# vivepos-v1-1.net
KiCad netlist of a schematic drawn in EAGLE
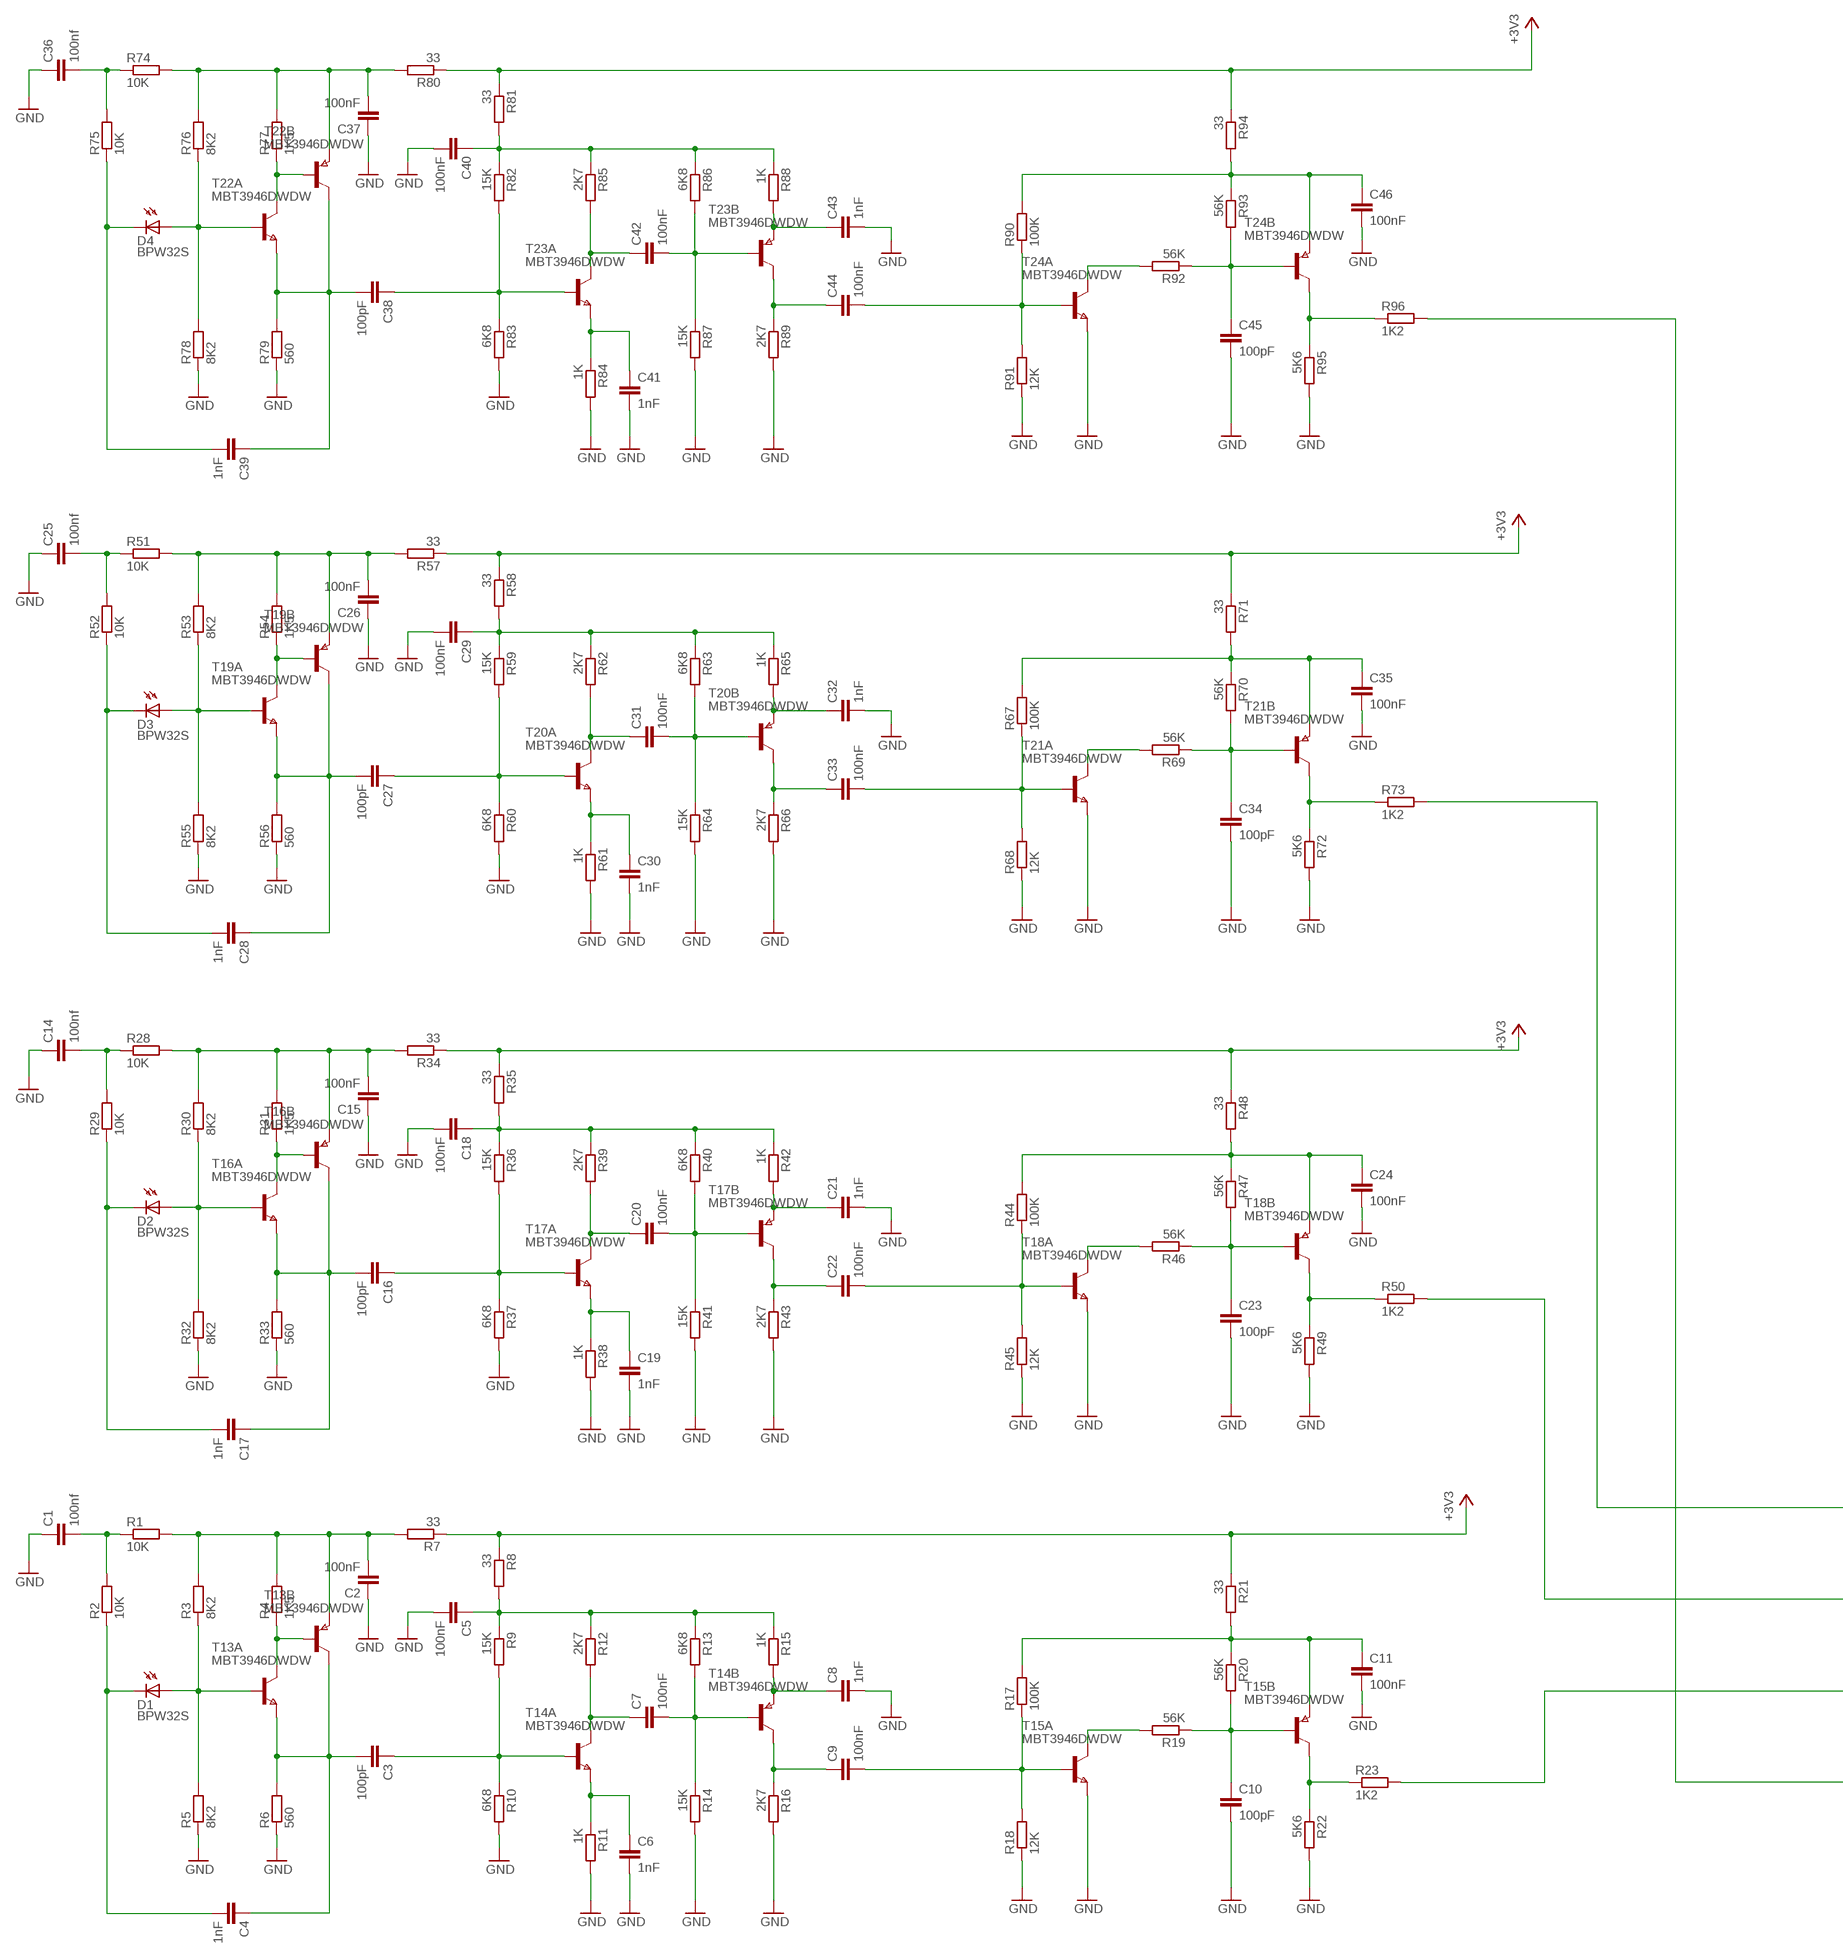
[diagram p0: schematic, sheet 1, part 1 of 2]
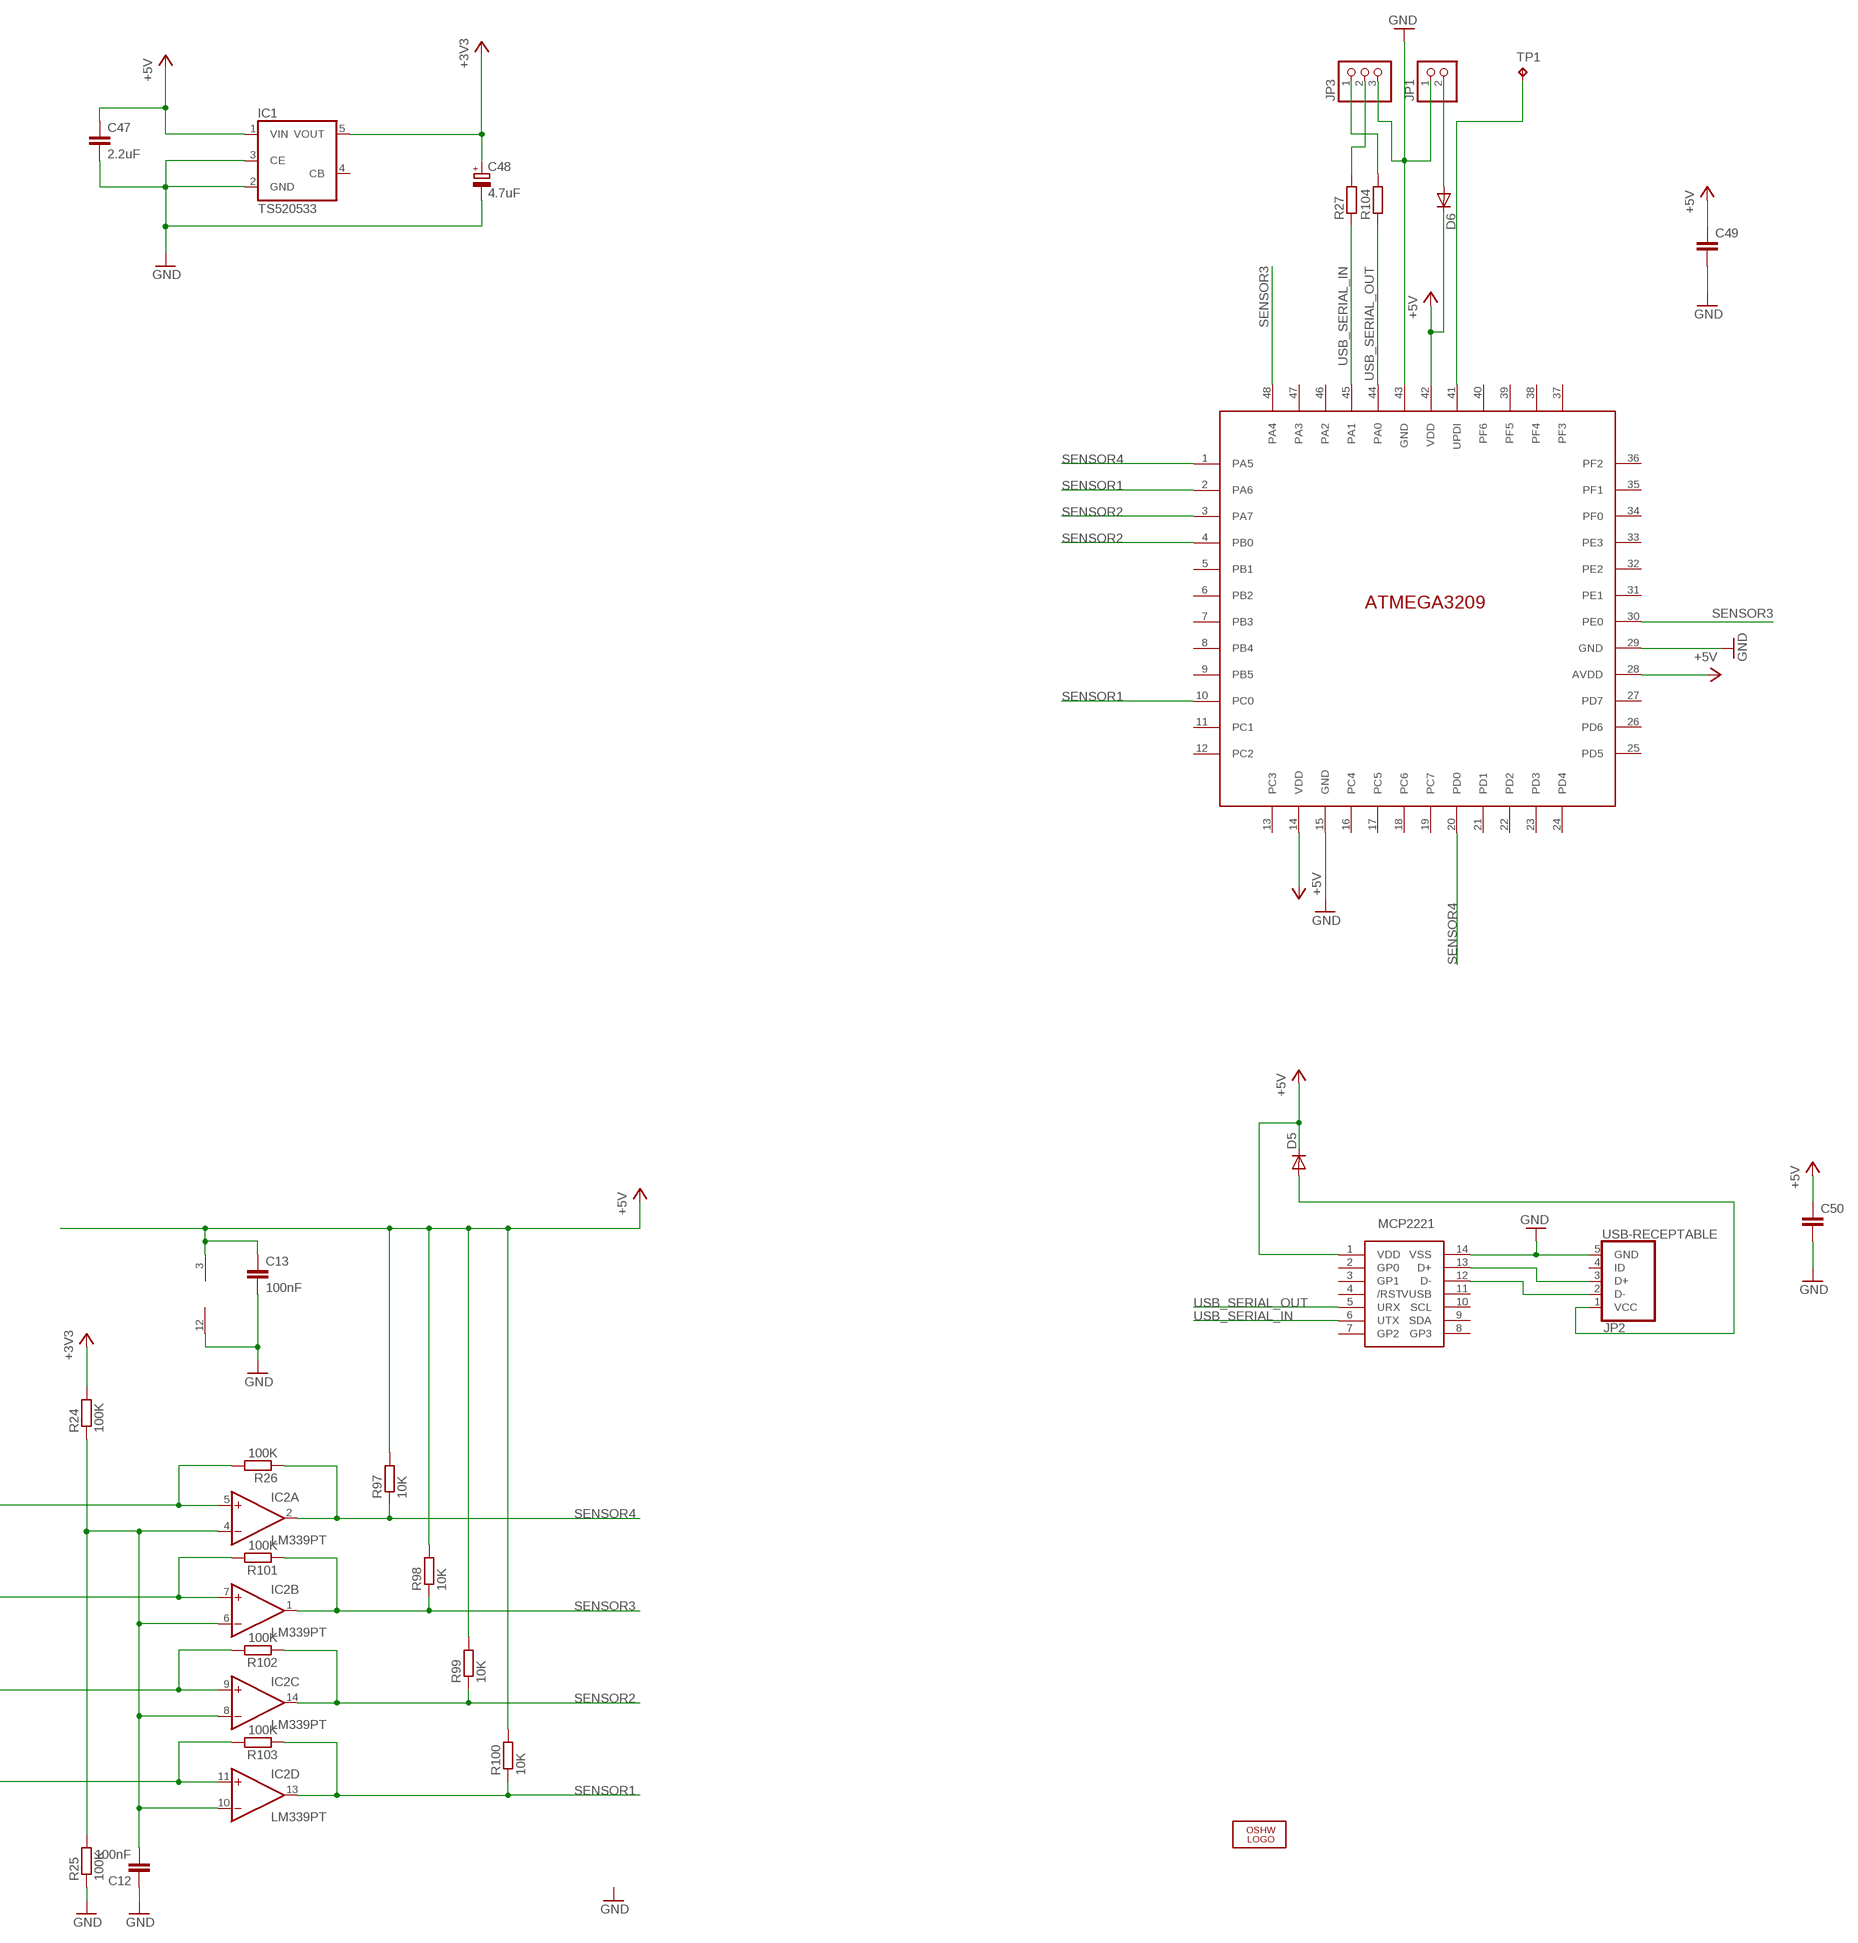
[diagram p1: schematic, sheet 1, part 2 of 2]

(export (version "E")
  (design (tool "Eeschema 10.0.6"))
  (components
    (comp (ref "C1")
      (value "100nf")
      (footprint "eagle-import:C0402")
      (libsource (lib "eagle-import") (part "C-EUC0402"))
    )
    (comp (ref "C2")
      (value "100nF")
      (footprint "eagle-import:C0402")
      (libsource (lib "eagle-import") (part "C-EUC0402"))
    )
    (comp (ref "C3")
      (value "100pF")
      (footprint "eagle-import:C0402")
      (libsource (lib "eagle-import") (part "C-EUC0402"))
    )
    (comp (ref "C4")
      (value "1nF")
      (footprint "eagle-import:C0402")
      (libsource (lib "eagle-import") (part "C-EUC0402"))
    )
    (comp (ref "C5")
      (value "100nF")
      (footprint "eagle-import:C0402")
      (libsource (lib "eagle-import") (part "C-EUC0402"))
    )
    (comp (ref "C6")
      (value "1nF")
      (footprint "eagle-import:C0402")
      (libsource (lib "eagle-import") (part "C-EUC0402"))
    )
    (comp (ref "C7")
      (value "100nF")
      (footprint "eagle-import:C0402")
      (libsource (lib "eagle-import") (part "C-EUC0402"))
    )
    (comp (ref "C8")
      (value "1nF")
      (footprint "eagle-import:C0402")
      (libsource (lib "eagle-import") (part "C-EUC0402"))
    )
    (comp (ref "C9")
      (value "100nF")
      (footprint "eagle-import:C0402")
      (libsource (lib "eagle-import") (part "C-EUC0402"))
    )
    (comp (ref "C10")
      (value "100pF")
      (footprint "eagle-import:C0402")
      (libsource (lib "eagle-import") (part "C-EUC0402"))
    )
    (comp (ref "C11")
      (value "100nF")
      (footprint "eagle-import:C0402")
      (libsource (lib "eagle-import") (part "C-EUC0402"))
    )
    (comp (ref "C12")
      (value "100nF")
      (footprint "eagle-import:C0402")
      (libsource (lib "eagle-import") (part "C-EUC0402"))
    )
    (comp (ref "C13")
      (value "100nF")
      (footprint "eagle-import:C0402")
      (libsource (lib "eagle-import") (part "C-EUC0402"))
    )
    (comp (ref "C14")
      (value "100nf")
      (footprint "eagle-import:C0402")
      (libsource (lib "eagle-import") (part "C-EUC0402"))
    )
    (comp (ref "C15")
      (value "100nF")
      (footprint "eagle-import:C0402")
      (libsource (lib "eagle-import") (part "C-EUC0402"))
    )
    (comp (ref "C16")
      (value "100pF")
      (footprint "eagle-import:C0402")
      (libsource (lib "eagle-import") (part "C-EUC0402"))
    )
    (comp (ref "C17")
      (value "1nF")
      (footprint "eagle-import:C0402")
      (libsource (lib "eagle-import") (part "C-EUC0402"))
    )
    (comp (ref "C18")
      (value "100nF")
      (footprint "eagle-import:C0402")
      (libsource (lib "eagle-import") (part "C-EUC0402"))
    )
    (comp (ref "C19")
      (value "1nF")
      (footprint "eagle-import:C0402")
      (libsource (lib "eagle-import") (part "C-EUC0402"))
    )
    (comp (ref "C20")
      (value "100nF")
      (footprint "eagle-import:C0402")
      (libsource (lib "eagle-import") (part "C-EUC0402"))
    )
    (comp (ref "C21")
      (value "1nF")
      (footprint "eagle-import:C0402")
      (libsource (lib "eagle-import") (part "C-EUC0402"))
    )
    (comp (ref "C22")
      (value "100nF")
      (footprint "eagle-import:C0402")
      (libsource (lib "eagle-import") (part "C-EUC0402"))
    )
    (comp (ref "C23")
      (value "100pF")
      (footprint "eagle-import:C0402")
      (libsource (lib "eagle-import") (part "C-EUC0402"))
    )
    (comp (ref "C24")
      (value "100nF")
      (footprint "eagle-import:C0402")
      (libsource (lib "eagle-import") (part "C-EUC0402"))
    )
    (comp (ref "C25")
      (value "100nf")
      (footprint "eagle-import:C0402")
      (libsource (lib "eagle-import") (part "C-EUC0402"))
    )
    (comp (ref "C26")
      (value "100nF")
      (footprint "eagle-import:C0402")
      (libsource (lib "eagle-import") (part "C-EUC0402"))
    )
    (comp (ref "C27")
      (value "100pF")
      (footprint "eagle-import:C0402")
      (libsource (lib "eagle-import") (part "C-EUC0402"))
    )
    (comp (ref "C28")
      (value "1nF")
      (footprint "eagle-import:C0402")
      (libsource (lib "eagle-import") (part "C-EUC0402"))
    )
    (comp (ref "C29")
      (value "100nF")
      (footprint "eagle-import:C0402")
      (libsource (lib "eagle-import") (part "C-EUC0402"))
    )
    (comp (ref "C30")
      (value "1nF")
      (footprint "eagle-import:C0402")
      (libsource (lib "eagle-import") (part "C-EUC0402"))
    )
    (comp (ref "C31")
      (value "100nF")
      (footprint "eagle-import:C0402")
      (libsource (lib "eagle-import") (part "C-EUC0402"))
    )
    (comp (ref "C32")
      (value "1nF")
      (footprint "eagle-import:C0402")
      (libsource (lib "eagle-import") (part "C-EUC0402"))
    )
    (comp (ref "C33")
      (value "100nF")
      (footprint "eagle-import:C0402")
      (libsource (lib "eagle-import") (part "C-EUC0402"))
    )
    (comp (ref "C34")
      (value "100pF")
      (footprint "eagle-import:C0402")
      (libsource (lib "eagle-import") (part "C-EUC0402"))
    )
    (comp (ref "C35")
      (value "100nF")
      (footprint "eagle-import:C0402")
      (libsource (lib "eagle-import") (part "C-EUC0402"))
    )
    (comp (ref "C36")
      (value "100nf")
      (footprint "eagle-import:C0402")
      (libsource (lib "eagle-import") (part "C-EUC0402"))
    )
    (comp (ref "C37")
      (value "100nF")
      (footprint "eagle-import:C0402")
      (libsource (lib "eagle-import") (part "C-EUC0402"))
    )
    (comp (ref "C38")
      (value "100pF")
      (footprint "eagle-import:C0402")
      (libsource (lib "eagle-import") (part "C-EUC0402"))
    )
    (comp (ref "C39")
      (value "1nF")
      (footprint "eagle-import:C0402")
      (libsource (lib "eagle-import") (part "C-EUC0402"))
    )
    (comp (ref "C40")
      (value "100nF")
      (footprint "eagle-import:C0402")
      (libsource (lib "eagle-import") (part "C-EUC0402"))
    )
    (comp (ref "C41")
      (value "1nF")
      (footprint "eagle-import:C0402")
      (libsource (lib "eagle-import") (part "C-EUC0402"))
    )
    (comp (ref "C42")
      (value "100nF")
      (footprint "eagle-import:C0402")
      (libsource (lib "eagle-import") (part "C-EUC0402"))
    )
    (comp (ref "C43")
      (value "1nF")
      (footprint "eagle-import:C0402")
      (libsource (lib "eagle-import") (part "C-EUC0402"))
    )
    (comp (ref "C44")
      (value "100nF")
      (footprint "eagle-import:C0402")
      (libsource (lib "eagle-import") (part "C-EUC0402"))
    )
    (comp (ref "C45")
      (value "100pF")
      (footprint "eagle-import:C0402")
      (libsource (lib "eagle-import") (part "C-EUC0402"))
    )
    (comp (ref "C46")
      (value "100nF")
      (footprint "eagle-import:C0402")
      (libsource (lib "eagle-import") (part "C-EUC0402"))
    )
    (comp (ref "C47")
      (value "2.2uF")
      (footprint "eagle-import:C0805")
      (libsource (lib "eagle-import") (part "C-EUC0805"))
    )
    (comp (ref "C48")
      (value "4.7uF")
      (footprint "eagle-import:B_3528-21R")
      (libsource (lib "eagle-import") (part "CPOL-EUB/3528-21R"))
    )
    (comp (ref "C49")
      (value "C-EUC0402")
      (footprint "eagle-import:C0402")
      (libsource (lib "eagle-import") (part "C-EUC0402"))
    )
    (comp (ref "C50")
      (value "C-EUC0603")
      (footprint "eagle-import:C0603")
      (libsource (lib "eagle-import") (part "C-EUC0603"))
    )
    (comp (ref "D1")
      (value "BPW32S")
      (footprint "eagle-import:BPW34S")
      (libsource (lib "eagle-import") (part "BPW32S"))
    )
    (comp (ref "D2")
      (value "BPW32S")
      (footprint "eagle-import:BPW34S")
      (libsource (lib "eagle-import") (part "BPW32S"))
    )
    (comp (ref "D3")
      (value "BPW32S")
      (footprint "eagle-import:BPW34S")
      (libsource (lib "eagle-import") (part "BPW32S"))
    )
    (comp (ref "D4")
      (value "BPW32S")
      (footprint "eagle-import:BPW34S")
      (libsource (lib "eagle-import") (part "BPW32S"))
    )
    (comp (ref "D5")
      (value "DIODE-SOD323-W")
      (footprint "eagle-import:SOD323-W")
      (libsource (lib "eagle-import") (part "DIODE-SOD323-W"))
    )
    (comp (ref "D6")
      (value "DIODE-SOD323-W")
      (footprint "eagle-import:SOD323-W")
      (libsource (lib "eagle-import") (part "DIODE-SOD323-W"))
    )
    (comp (ref "IC1")
      (value "TS520533")
      (footprint "eagle-import:SOT25")
      (libsource (lib "eagle-import") (part "TS520533"))
    )
    (comp (ref "IC2")
      (value "LM339PT")
      (footprint "eagle-import:TSSOP14")
      (libsource (lib "eagle-import") (part "LM339PT"))
    )
    (comp (ref "JP1")
      (value "PINHD-1X2")
      (footprint "eagle-import:1X02")
      (libsource (lib "eagle-import") (part "PINHD-1X2"))
    )
    (comp (ref "JP2")
      (value "USB-RECEPTABLE")
      (footprint "eagle-import:FCI-10103594-0001LF")
      (libsource (lib "eagle-import") (part "USB-RECEPTABLE"))
    )
    (comp (ref "JP3")
      (value "PINHD-1X3")
      (footprint "eagle-import:1X03")
      (libsource (lib "eagle-import") (part "PINHD-1X3"))
    )
    (comp (ref "LOGO1")
      (value "OSHW_LOGO_FILLX0200-NT")
      (footprint "eagle-import:OSHW_FILLX200_NOTEXT")
      (libsource (lib "eagle-import") (part "OSHW_LOGO_FILLX0200-NT"))
    )
    (comp (ref "R1")
      (value "10K")
      (footprint "eagle-import:R0402")
      (libsource (lib "eagle-import") (part "R-EU_R0402"))
    )
    (comp (ref "R2")
      (value "10K")
      (footprint "eagle-import:R0402")
      (libsource (lib "eagle-import") (part "R-EU_R0402"))
    )
    (comp (ref "R3")
      (value "8K2")
      (footprint "eagle-import:R0402")
      (libsource (lib "eagle-import") (part "R-EU_R0402"))
    )
    (comp (ref "R4")
      (value "1K5")
      (footprint "eagle-import:R0402")
      (libsource (lib "eagle-import") (part "R-EU_R0402"))
    )
    (comp (ref "R5")
      (value "8K2")
      (footprint "eagle-import:R0402")
      (libsource (lib "eagle-import") (part "R-EU_R0402"))
    )
    (comp (ref "R6")
      (value "560")
      (footprint "eagle-import:R0402")
      (libsource (lib "eagle-import") (part "R-EU_R0402"))
    )
    (comp (ref "R7")
      (value "33")
      (footprint "eagle-import:R0402")
      (libsource (lib "eagle-import") (part "R-EU_R0402"))
    )
    (comp (ref "R8")
      (value "33")
      (footprint "eagle-import:R0402")
      (libsource (lib "eagle-import") (part "R-EU_R0402"))
    )
    (comp (ref "R9")
      (value "15K")
      (footprint "eagle-import:R0402")
      (libsource (lib "eagle-import") (part "R-EU_R0402"))
    )
    (comp (ref "R10")
      (value "6K8")
      (footprint "eagle-import:R0402")
      (libsource (lib "eagle-import") (part "R-EU_R0402"))
    )
    (comp (ref "R11")
      (value "1K")
      (footprint "eagle-import:R0402")
      (libsource (lib "eagle-import") (part "R-EU_R0402"))
    )
    (comp (ref "R12")
      (value "2K7")
      (footprint "eagle-import:R0402")
      (libsource (lib "eagle-import") (part "R-EU_R0402"))
    )
    (comp (ref "R13")
      (value "6K8")
      (footprint "eagle-import:R0402")
      (libsource (lib "eagle-import") (part "R-EU_R0402"))
    )
    (comp (ref "R14")
      (value "15K")
      (footprint "eagle-import:R0402")
      (libsource (lib "eagle-import") (part "R-EU_R0402"))
    )
    (comp (ref "R15")
      (value "1K")
      (footprint "eagle-import:R0402")
      (libsource (lib "eagle-import") (part "R-EU_R0402"))
    )
    (comp (ref "R16")
      (value "2K7")
      (footprint "eagle-import:R0402")
      (libsource (lib "eagle-import") (part "R-EU_R0402"))
    )
    (comp (ref "R17")
      (value "100K")
      (footprint "eagle-import:R0402")
      (libsource (lib "eagle-import") (part "R-EU_R0402"))
    )
    (comp (ref "R18")
      (value "12K")
      (footprint "eagle-import:R0402")
      (libsource (lib "eagle-import") (part "R-EU_R0402"))
    )
    (comp (ref "R19")
      (value "56K")
      (footprint "eagle-import:R0402")
      (libsource (lib "eagle-import") (part "R-EU_R0402"))
    )
    (comp (ref "R20")
      (value "56K")
      (footprint "eagle-import:R0402")
      (libsource (lib "eagle-import") (part "R-EU_R0402"))
    )
    (comp (ref "R21")
      (value "33")
      (footprint "eagle-import:R0402")
      (libsource (lib "eagle-import") (part "R-EU_R0402"))
    )
    (comp (ref "R22")
      (value "5K6")
      (footprint "eagle-import:R0402")
      (libsource (lib "eagle-import") (part "R-EU_R0402"))
    )
    (comp (ref "R23")
      (value "1K2")
      (footprint "eagle-import:R0402")
      (libsource (lib "eagle-import") (part "R-EU_R0402"))
    )
    (comp (ref "R24")
      (value "100K")
      (footprint "eagle-import:R0402")
      (libsource (lib "eagle-import") (part "R-EU_R0402"))
    )
    (comp (ref "R25")
      (value "100K")
      (footprint "eagle-import:R0402")
      (libsource (lib "eagle-import") (part "R-EU_R0402"))
    )
    (comp (ref "R26")
      (value "100K")
      (footprint "eagle-import:R0402")
      (libsource (lib "eagle-import") (part "R-EU_R0402"))
    )
    (comp (ref "R27")
      (value "R-EU_R0402")
      (footprint "eagle-import:R0402")
      (libsource (lib "eagle-import") (part "R-EU_R0402"))
    )
    (comp (ref "R28")
      (value "10K")
      (footprint "eagle-import:R0402")
      (libsource (lib "eagle-import") (part "R-EU_R0402"))
    )
    (comp (ref "R29")
      (value "10K")
      (footprint "eagle-import:R0402")
      (libsource (lib "eagle-import") (part "R-EU_R0402"))
    )
    (comp (ref "R30")
      (value "8K2")
      (footprint "eagle-import:R0402")
      (libsource (lib "eagle-import") (part "R-EU_R0402"))
    )
    (comp (ref "R31")
      (value "1K5")
      (footprint "eagle-import:R0402")
      (libsource (lib "eagle-import") (part "R-EU_R0402"))
    )
    (comp (ref "R32")
      (value "8K2")
      (footprint "eagle-import:R0402")
      (libsource (lib "eagle-import") (part "R-EU_R0402"))
    )
    (comp (ref "R33")
      (value "560")
      (footprint "eagle-import:R0402")
      (libsource (lib "eagle-import") (part "R-EU_R0402"))
    )
    (comp (ref "R34")
      (value "33")
      (footprint "eagle-import:R0402")
      (libsource (lib "eagle-import") (part "R-EU_R0402"))
    )
    (comp (ref "R35")
      (value "33")
      (footprint "eagle-import:R0402")
      (libsource (lib "eagle-import") (part "R-EU_R0402"))
    )
    (comp (ref "R36")
      (value "15K")
      (footprint "eagle-import:R0402")
      (libsource (lib "eagle-import") (part "R-EU_R0402"))
    )
    (comp (ref "R37")
      (value "6K8")
      (footprint "eagle-import:R0402")
      (libsource (lib "eagle-import") (part "R-EU_R0402"))
    )
    (comp (ref "R38")
      (value "1K")
      (footprint "eagle-import:R0402")
      (libsource (lib "eagle-import") (part "R-EU_R0402"))
    )
    (comp (ref "R39")
      (value "2K7")
      (footprint "eagle-import:R0402")
      (libsource (lib "eagle-import") (part "R-EU_R0402"))
    )
    (comp (ref "R40")
      (value "6K8")
      (footprint "eagle-import:R0402")
      (libsource (lib "eagle-import") (part "R-EU_R0402"))
    )
    (comp (ref "R41")
      (value "15K")
      (footprint "eagle-import:R0402")
      (libsource (lib "eagle-import") (part "R-EU_R0402"))
    )
    (comp (ref "R42")
      (value "1K")
      (footprint "eagle-import:R0402")
      (libsource (lib "eagle-import") (part "R-EU_R0402"))
    )
    (comp (ref "R43")
      (value "2K7")
      (footprint "eagle-import:R0402")
      (libsource (lib "eagle-import") (part "R-EU_R0402"))
    )
    (comp (ref "R44")
      (value "100K")
      (footprint "eagle-import:R0402")
      (libsource (lib "eagle-import") (part "R-EU_R0402"))
    )
    (comp (ref "R45")
      (value "12K")
      (footprint "eagle-import:R0402")
      (libsource (lib "eagle-import") (part "R-EU_R0402"))
    )
    (comp (ref "R46")
      (value "56K")
      (footprint "eagle-import:R0402")
      (libsource (lib "eagle-import") (part "R-EU_R0402"))
    )
    (comp (ref "R47")
      (value "56K")
      (footprint "eagle-import:R0402")
      (libsource (lib "eagle-import") (part "R-EU_R0402"))
    )
    (comp (ref "R48")
      (value "33")
      (footprint "eagle-import:R0402")
      (libsource (lib "eagle-import") (part "R-EU_R0402"))
    )
    (comp (ref "R49")
      (value "5K6")
      (footprint "eagle-import:R0402")
      (libsource (lib "eagle-import") (part "R-EU_R0402"))
    )
    (comp (ref "R50")
      (value "1K2")
      (footprint "eagle-import:R0402")
      (libsource (lib "eagle-import") (part "R-EU_R0402"))
    )
    (comp (ref "R51")
      (value "10K")
      (footprint "eagle-import:R0402")
      (libsource (lib "eagle-import") (part "R-EU_R0402"))
    )
    (comp (ref "R52")
      (value "10K")
      (footprint "eagle-import:R0402")
      (libsource (lib "eagle-import") (part "R-EU_R0402"))
    )
    (comp (ref "R53")
      (value "8K2")
      (footprint "eagle-import:R0402")
      (libsource (lib "eagle-import") (part "R-EU_R0402"))
    )
    (comp (ref "R54")
      (value "1K5")
      (footprint "eagle-import:R0402")
      (libsource (lib "eagle-import") (part "R-EU_R0402"))
    )
    (comp (ref "R55")
      (value "8K2")
      (footprint "eagle-import:R0402")
      (libsource (lib "eagle-import") (part "R-EU_R0402"))
    )
    (comp (ref "R56")
      (value "560")
      (footprint "eagle-import:R0402")
      (libsource (lib "eagle-import") (part "R-EU_R0402"))
    )
    (comp (ref "R57")
      (value "33")
      (footprint "eagle-import:R0402")
      (libsource (lib "eagle-import") (part "R-EU_R0402"))
    )
    (comp (ref "R58")
      (value "33")
      (footprint "eagle-import:R0402")
      (libsource (lib "eagle-import") (part "R-EU_R0402"))
    )
    (comp (ref "R59")
      (value "15K")
      (footprint "eagle-import:R0402")
      (libsource (lib "eagle-import") (part "R-EU_R0402"))
    )
    (comp (ref "R60")
      (value "6K8")
      (footprint "eagle-import:R0402")
      (libsource (lib "eagle-import") (part "R-EU_R0402"))
    )
    (comp (ref "R61")
      (value "1K")
      (footprint "eagle-import:R0402")
      (libsource (lib "eagle-import") (part "R-EU_R0402"))
    )
    (comp (ref "R62")
      (value "2K7")
      (footprint "eagle-import:R0402")
      (libsource (lib "eagle-import") (part "R-EU_R0402"))
    )
    (comp (ref "R63")
      (value "6K8")
      (footprint "eagle-import:R0402")
      (libsource (lib "eagle-import") (part "R-EU_R0402"))
    )
    (comp (ref "R64")
      (value "15K")
      (footprint "eagle-import:R0402")
      (libsource (lib "eagle-import") (part "R-EU_R0402"))
    )
    (comp (ref "R65")
      (value "1K")
      (footprint "eagle-import:R0402")
      (libsource (lib "eagle-import") (part "R-EU_R0402"))
    )
    (comp (ref "R66")
      (value "2K7")
      (footprint "eagle-import:R0402")
      (libsource (lib "eagle-import") (part "R-EU_R0402"))
    )
    (comp (ref "R67")
      (value "100K")
      (footprint "eagle-import:R0402")
      (libsource (lib "eagle-import") (part "R-EU_R0402"))
    )
    (comp (ref "R68")
      (value "12K")
      (footprint "eagle-import:R0402")
      (libsource (lib "eagle-import") (part "R-EU_R0402"))
    )
    (comp (ref "R69")
      (value "56K")
      (footprint "eagle-import:R0402")
      (libsource (lib "eagle-import") (part "R-EU_R0402"))
    )
    (comp (ref "R70")
      (value "56K")
      (footprint "eagle-import:R0402")
      (libsource (lib "eagle-import") (part "R-EU_R0402"))
    )
    (comp (ref "R71")
      (value "33")
      (footprint "eagle-import:R0402")
      (libsource (lib "eagle-import") (part "R-EU_R0402"))
    )
    (comp (ref "R72")
      (value "5K6")
      (footprint "eagle-import:R0402")
      (libsource (lib "eagle-import") (part "R-EU_R0402"))
    )
    (comp (ref "R73")
      (value "1K2")
      (footprint "eagle-import:R0402")
      (libsource (lib "eagle-import") (part "R-EU_R0402"))
    )
    (comp (ref "R74")
      (value "10K")
      (footprint "eagle-import:R0402")
      (libsource (lib "eagle-import") (part "R-EU_R0402"))
    )
    (comp (ref "R75")
      (value "10K")
      (footprint "eagle-import:R0402")
      (libsource (lib "eagle-import") (part "R-EU_R0402"))
    )
    (comp (ref "R76")
      (value "8K2")
      (footprint "eagle-import:R0402")
      (libsource (lib "eagle-import") (part "R-EU_R0402"))
    )
    (comp (ref "R77")
      (value "1K5")
      (footprint "eagle-import:R0402")
      (libsource (lib "eagle-import") (part "R-EU_R0402"))
    )
    (comp (ref "R78")
      (value "8K2")
      (footprint "eagle-import:R0402")
      (libsource (lib "eagle-import") (part "R-EU_R0402"))
    )
    (comp (ref "R79")
      (value "560")
      (footprint "eagle-import:R0402")
      (libsource (lib "eagle-import") (part "R-EU_R0402"))
    )
    (comp (ref "R80")
      (value "33")
      (footprint "eagle-import:R0402")
      (libsource (lib "eagle-import") (part "R-EU_R0402"))
    )
    (comp (ref "R81")
      (value "33")
      (footprint "eagle-import:R0402")
      (libsource (lib "eagle-import") (part "R-EU_R0402"))
    )
    (comp (ref "R82")
      (value "15K")
      (footprint "eagle-import:R0402")
      (libsource (lib "eagle-import") (part "R-EU_R0402"))
    )
    (comp (ref "R83")
      (value "6K8")
      (footprint "eagle-import:R0402")
      (libsource (lib "eagle-import") (part "R-EU_R0402"))
    )
    (comp (ref "R84")
      (value "1K")
      (footprint "eagle-import:R0402")
      (libsource (lib "eagle-import") (part "R-EU_R0402"))
    )
    (comp (ref "R85")
      (value "2K7")
      (footprint "eagle-import:R0402")
      (libsource (lib "eagle-import") (part "R-EU_R0402"))
    )
    (comp (ref "R86")
      (value "6K8")
      (footprint "eagle-import:R0402")
      (libsource (lib "eagle-import") (part "R-EU_R0402"))
    )
    (comp (ref "R87")
      (value "15K")
      (footprint "eagle-import:R0402")
      (libsource (lib "eagle-import") (part "R-EU_R0402"))
    )
    (comp (ref "R88")
      (value "1K")
      (footprint "eagle-import:R0402")
      (libsource (lib "eagle-import") (part "R-EU_R0402"))
    )
    (comp (ref "R89")
      (value "2K7")
      (footprint "eagle-import:R0402")
      (libsource (lib "eagle-import") (part "R-EU_R0402"))
    )
    (comp (ref "R90")
      (value "100K")
      (footprint "eagle-import:R0402")
      (libsource (lib "eagle-import") (part "R-EU_R0402"))
    )
    (comp (ref "R91")
      (value "12K")
      (footprint "eagle-import:R0402")
      (libsource (lib "eagle-import") (part "R-EU_R0402"))
    )
    (comp (ref "R92")
      (value "56K")
      (footprint "eagle-import:R0402")
      (libsource (lib "eagle-import") (part "R-EU_R0402"))
    )
    (comp (ref "R93")
      (value "56K")
      (footprint "eagle-import:R0402")
      (libsource (lib "eagle-import") (part "R-EU_R0402"))
    )
    (comp (ref "R94")
      (value "33")
      (footprint "eagle-import:R0402")
      (libsource (lib "eagle-import") (part "R-EU_R0402"))
    )
    (comp (ref "R95")
      (value "5K6")
      (footprint "eagle-import:R0402")
      (libsource (lib "eagle-import") (part "R-EU_R0402"))
    )
    (comp (ref "R96")
      (value "1K2")
      (footprint "eagle-import:R0402")
      (libsource (lib "eagle-import") (part "R-EU_R0402"))
    )
    (comp (ref "R97")
      (value "10K")
      (footprint "eagle-import:R0402")
      (libsource (lib "eagle-import") (part "R-EU_R0402"))
    )
    (comp (ref "R98")
      (value "10K")
      (footprint "eagle-import:R0402")
      (libsource (lib "eagle-import") (part "R-EU_R0402"))
    )
    (comp (ref "R99")
      (value "10K")
      (footprint "eagle-import:R0402")
      (libsource (lib "eagle-import") (part "R-EU_R0402"))
    )
    (comp (ref "R100")
      (value "10K")
      (footprint "eagle-import:R0402")
      (libsource (lib "eagle-import") (part "R-EU_R0402"))
    )
    (comp (ref "R101")
      (value "100K")
      (footprint "eagle-import:R0402")
      (libsource (lib "eagle-import") (part "R-EU_R0402"))
    )
    (comp (ref "R102")
      (value "100K")
      (footprint "eagle-import:R0402")
      (libsource (lib "eagle-import") (part "R-EU_R0402"))
    )
    (comp (ref "R103")
      (value "100K")
      (footprint "eagle-import:R0402")
      (libsource (lib "eagle-import") (part "R-EU_R0402"))
    )
    (comp (ref "R104")
      (value "R-EU_R0402")
      (footprint "eagle-import:R0402")
      (libsource (lib "eagle-import") (part "R-EU_R0402"))
    )
    (comp (ref "T13")
      (value "MBT3946DWDW")
      (footprint "eagle-import:SOT363_PHILIPS")
      (libsource (lib "eagle-import") (part "MBT3946DWDW"))
    )
    (comp (ref "T14")
      (value "MBT3946DWDW")
      (footprint "eagle-import:SOT363_PHILIPS")
      (libsource (lib "eagle-import") (part "MBT3946DWDW"))
    )
    (comp (ref "T15")
      (value "MBT3946DWDW")
      (footprint "eagle-import:SOT363_PHILIPS")
      (libsource (lib "eagle-import") (part "MBT3946DWDW"))
    )
    (comp (ref "T16")
      (value "MBT3946DWDW")
      (footprint "eagle-import:SOT363_PHILIPS")
      (libsource (lib "eagle-import") (part "MBT3946DWDW"))
    )
    (comp (ref "T17")
      (value "MBT3946DWDW")
      (footprint "eagle-import:SOT363_PHILIPS")
      (libsource (lib "eagle-import") (part "MBT3946DWDW"))
    )
    (comp (ref "T18")
      (value "MBT3946DWDW")
      (footprint "eagle-import:SOT363_PHILIPS")
      (libsource (lib "eagle-import") (part "MBT3946DWDW"))
    )
    (comp (ref "T19")
      (value "MBT3946DWDW")
      (footprint "eagle-import:SOT363_PHILIPS")
      (libsource (lib "eagle-import") (part "MBT3946DWDW"))
    )
    (comp (ref "T20")
      (value "MBT3946DWDW")
      (footprint "eagle-import:SOT363_PHILIPS")
      (libsource (lib "eagle-import") (part "MBT3946DWDW"))
    )
    (comp (ref "T21")
      (value "MBT3946DWDW")
      (footprint "eagle-import:SOT363_PHILIPS")
      (libsource (lib "eagle-import") (part "MBT3946DWDW"))
    )
    (comp (ref "T22")
      (value "MBT3946DWDW")
      (footprint "eagle-import:SOT363_PHILIPS")
      (libsource (lib "eagle-import") (part "MBT3946DWDW"))
    )
    (comp (ref "T23")
      (value "MBT3946DWDW")
      (footprint "eagle-import:SOT363_PHILIPS")
      (libsource (lib "eagle-import") (part "MBT3946DWDW"))
    )
    (comp (ref "T24")
      (value "MBT3946DWDW")
      (footprint "eagle-import:SOT363_PHILIPS")
      (libsource (lib "eagle-import") (part "MBT3946DWDW"))
    )
    (comp (ref "TP1")
      (value "TPTP15R")
      (footprint "eagle-import:TP15R")
      (libsource (lib "eagle-import") (part "TPTP15R"))
    )
    (comp (ref "U$1")
      (value "MCP2221")
      (footprint "eagle-import:SOIC14")
      (libsource (lib "eagle-import") (part "MCP2221"))
    )
    (comp (ref "U$2")
      (value "ATMEGA3209")
      (footprint "eagle-import:TQFP48")
      (libsource (lib "eagle-import") (part "ATMEGA3209"))
    )
  )
  (nets
    (net (code "1") (name "+3V3") (class "Default")
      (node (ref "C48") (pin "+") (pinfunction "+_+") (pintype "passive"))
      (node (ref "IC1") (pin "5") (pinfunction "VOUT_5") (pintype "passive"))
      (node (ref "R21") (pin "1") (pinfunction "1_1") (pintype "passive"))
      (node (ref "R24") (pin "2") (pinfunction "2_2") (pintype "passive"))
      (node (ref "R34") (pin "1") (pinfunction "1_1") (pintype "passive"))
      (node (ref "R35") (pin "1") (pinfunction "1_1") (pintype "passive"))
      (node (ref "R48") (pin "1") (pinfunction "1_1") (pintype "passive"))
      (node (ref "R57") (pin "1") (pinfunction "1_1") (pintype "passive"))
      (node (ref "R58") (pin "1") (pinfunction "1_1") (pintype "passive"))
      (node (ref "R7") (pin "1") (pinfunction "1_1") (pintype "passive"))
      (node (ref "R71") (pin "1") (pinfunction "1_1") (pintype "passive"))
      (node (ref "R8") (pin "1") (pinfunction "1_1") (pintype "passive"))
      (node (ref "R80") (pin "1") (pinfunction "1_1") (pintype "passive"))
      (node (ref "R81") (pin "1") (pinfunction "1_1") (pintype "passive"))
      (node (ref "R94") (pin "1") (pinfunction "1_1") (pintype "passive"))
    )
    (net (code "2") (name "+5V") (class "Default")
      (node (ref "C13") (pin "1") (pinfunction "1_1") (pintype "passive"))
      (node (ref "C47") (pin "1") (pinfunction "1_1") (pintype "passive"))
      (node (ref "C49") (pin "1") (pinfunction "1_1") (pintype "passive"))
      (node (ref "C50") (pin "1") (pinfunction "1_1") (pintype "passive"))
      (node (ref "D5") (pin "C") (pinfunction "C_C") (pintype "passive"))
      (node (ref "D6") (pin "C") (pinfunction "C_C") (pintype "passive"))
      (node (ref "IC1") (pin "1") (pinfunction "VIN_1") (pintype "input"))
      (node (ref "IC2") (pin "3") (pinfunction "V+_3") (pintype "power_in"))
      (node (ref "R100") (pin "2") (pinfunction "2_2") (pintype "passive"))
      (node (ref "R97") (pin "2") (pinfunction "2_2") (pintype "passive"))
      (node (ref "R98") (pin "2") (pinfunction "2_2") (pintype "passive"))
      (node (ref "R99") (pin "2") (pinfunction "2_2") (pintype "passive"))
      (node (ref "U$1") (pin "1") (pinfunction "VDD_1") (pintype "bidirectional"))
      (node (ref "U$2") (pin "14") (pinfunction "VDD_14") (pintype "bidirectional"))
      (node (ref "U$2") (pin "28") (pinfunction "AVDD_28") (pintype "bidirectional"))
      (node (ref "U$2") (pin "42") (pinfunction "VDD_42") (pintype "bidirectional"))
    )
    (net (code "3") (name "/SENSOR1") (class "Default")
      (node (ref "IC2") (pin "13") (pinfunction "OUT_13") (pintype "open_collector"))
      (node (ref "R100") (pin "1") (pinfunction "1_1") (pintype "passive"))
      (node (ref "R103") (pin "1") (pinfunction "1_1") (pintype "passive"))
      (node (ref "U$2") (pin "10") (pinfunction "PC0_10") (pintype "bidirectional"))
      (node (ref "U$2") (pin "2") (pinfunction "PA6_2") (pintype "bidirectional"))
    )
    (net (code "4") (name "/SENSOR2") (class "Default")
      (node (ref "IC2") (pin "14") (pinfunction "OUT_14") (pintype "open_collector"))
      (node (ref "R102") (pin "1") (pinfunction "1_1") (pintype "passive"))
      (node (ref "R99") (pin "1") (pinfunction "1_1") (pintype "passive"))
      (node (ref "U$2") (pin "3") (pinfunction "PA7_3") (pintype "bidirectional"))
      (node (ref "U$2") (pin "4") (pinfunction "PB0_4") (pintype "bidirectional"))
    )
    (net (code "5") (name "/SENSOR3") (class "Default")
      (node (ref "IC2") (pin "1") (pinfunction "OUT_1") (pintype "open_collector"))
      (node (ref "R101") (pin "1") (pinfunction "1_1") (pintype "passive"))
      (node (ref "R98") (pin "1") (pinfunction "1_1") (pintype "passive"))
      (node (ref "U$2") (pin "30") (pinfunction "PE0_30") (pintype "bidirectional"))
      (node (ref "U$2") (pin "48") (pinfunction "PA4_48") (pintype "bidirectional"))
    )
    (net (code "6") (name "/SENSOR4") (class "Default")
      (node (ref "IC2") (pin "2") (pinfunction "OUT_2") (pintype "open_collector"))
      (node (ref "R26") (pin "1") (pinfunction "1_1") (pintype "passive"))
      (node (ref "R97") (pin "1") (pinfunction "1_1") (pintype "passive"))
      (node (ref "U$2") (pin "1") (pinfunction "PA5_1") (pintype "bidirectional"))
      (node (ref "U$2") (pin "20") (pinfunction "PD0_20") (pintype "bidirectional"))
    )
    (net (code "7") (name "/USB_SERIAL_IN") (class "Default")
      (node (ref "R27") (pin "1") (pinfunction "1_1") (pintype "passive"))
      (node (ref "U$1") (pin "6") (pinfunction "UTX_6") (pintype "bidirectional"))
      (node (ref "U$2") (pin "45") (pinfunction "PA1_45") (pintype "bidirectional"))
    )
    (net (code "8") (name "/USB_SERIAL_OUT") (class "Default")
      (node (ref "R104") (pin "1") (pinfunction "1_1") (pintype "passive"))
      (node (ref "U$1") (pin "5") (pinfunction "URX_5") (pintype "bidirectional"))
      (node (ref "U$2") (pin "44") (pinfunction "PA0_44") (pintype "bidirectional"))
    )
    (net (code "9") (name "GND") (class "Default")
      (node (ref "C1") (pin "1") (pinfunction "1_1") (pintype "passive"))
      (node (ref "C10") (pin "2") (pinfunction "2_2") (pintype "passive"))
      (node (ref "C11") (pin "2") (pinfunction "2_2") (pintype "passive"))
      (node (ref "C12") (pin "1") (pinfunction "1_1") (pintype "passive"))
      (node (ref "C13") (pin "2") (pinfunction "2_2") (pintype "passive"))
      (node (ref "C14") (pin "1") (pinfunction "1_1") (pintype "passive"))
      (node (ref "C15") (pin "1") (pinfunction "1_1") (pintype "passive"))
      (node (ref "C18") (pin "2") (pinfunction "2_2") (pintype "passive"))
      (node (ref "C19") (pin "2") (pinfunction "2_2") (pintype "passive"))
      (node (ref "C2") (pin "1") (pinfunction "1_1") (pintype "passive"))
      (node (ref "C21") (pin "2") (pinfunction "2_2") (pintype "passive"))
      (node (ref "C23") (pin "2") (pinfunction "2_2") (pintype "passive"))
      (node (ref "C24") (pin "2") (pinfunction "2_2") (pintype "passive"))
      (node (ref "C25") (pin "1") (pinfunction "1_1") (pintype "passive"))
      (node (ref "C26") (pin "1") (pinfunction "1_1") (pintype "passive"))
      (node (ref "C29") (pin "2") (pinfunction "2_2") (pintype "passive"))
      (node (ref "C30") (pin "2") (pinfunction "2_2") (pintype "passive"))
      (node (ref "C32") (pin "2") (pinfunction "2_2") (pintype "passive"))
      (node (ref "C34") (pin "2") (pinfunction "2_2") (pintype "passive"))
      (node (ref "C35") (pin "2") (pinfunction "2_2") (pintype "passive"))
      (node (ref "C36") (pin "1") (pinfunction "1_1") (pintype "passive"))
      (node (ref "C37") (pin "1") (pinfunction "1_1") (pintype "passive"))
      (node (ref "C40") (pin "2") (pinfunction "2_2") (pintype "passive"))
      (node (ref "C41") (pin "2") (pinfunction "2_2") (pintype "passive"))
      (node (ref "C43") (pin "2") (pinfunction "2_2") (pintype "passive"))
      (node (ref "C45") (pin "2") (pinfunction "2_2") (pintype "passive"))
      (node (ref "C46") (pin "2") (pinfunction "2_2") (pintype "passive"))
      (node (ref "C47") (pin "2") (pinfunction "2_2") (pintype "passive"))
      (node (ref "C48") (pin "-") (pinfunction "-_-") (pintype "passive"))
      (node (ref "C49") (pin "2") (pinfunction "2_2") (pintype "passive"))
      (node (ref "C5") (pin "2") (pinfunction "2_2") (pintype "passive"))
      (node (ref "C50") (pin "2") (pinfunction "2_2") (pintype "passive"))
      (node (ref "C6") (pin "2") (pinfunction "2_2") (pintype "passive"))
      (node (ref "C8") (pin "2") (pinfunction "2_2") (pintype "passive"))
      (node (ref "IC1") (pin "2") (pinfunction "GND_2") (pintype "passive"))
      (node (ref "IC1") (pin "3") (pinfunction "CE_3") (pintype "input"))
      (node (ref "IC2") (pin "12") (pinfunction "GND_12") (pintype "power_in"))
      (node (ref "JP1") (pin "1") (pinfunction "1_1") (pintype "passive"))
      (node (ref "JP2") (pin "5") (pinfunction "GND_5") (pintype "bidirectional"))
      (node (ref "JP3") (pin "3") (pinfunction "3_3") (pintype "passive"))
      (node (ref "R10") (pin "2") (pinfunction "2_2") (pintype "passive"))
      (node (ref "R11") (pin "2") (pinfunction "2_2") (pintype "passive"))
      (node (ref "R14") (pin "2") (pinfunction "2_2") (pintype "passive"))
      (node (ref "R16") (pin "2") (pinfunction "2_2") (pintype "passive"))
      (node (ref "R18") (pin "1") (pinfunction "1_1") (pintype "passive"))
      (node (ref "R22") (pin "2") (pinfunction "2_2") (pintype "passive"))
      (node (ref "R25") (pin "1") (pinfunction "1_1") (pintype "passive"))
      (node (ref "R32") (pin "1") (pinfunction "1_1") (pintype "passive"))
      (node (ref "R33") (pin "1") (pinfunction "1_1") (pintype "passive"))
      (node (ref "R37") (pin "2") (pinfunction "2_2") (pintype "passive"))
      (node (ref "R38") (pin "2") (pinfunction "2_2") (pintype "passive"))
      (node (ref "R41") (pin "2") (pinfunction "2_2") (pintype "passive"))
      (node (ref "R43") (pin "2") (pinfunction "2_2") (pintype "passive"))
      (node (ref "R45") (pin "1") (pinfunction "1_1") (pintype "passive"))
      (node (ref "R49") (pin "2") (pinfunction "2_2") (pintype "passive"))
      (node (ref "R5") (pin "1") (pinfunction "1_1") (pintype "passive"))
      (node (ref "R55") (pin "1") (pinfunction "1_1") (pintype "passive"))
      (node (ref "R56") (pin "1") (pinfunction "1_1") (pintype "passive"))
      (node (ref "R6") (pin "1") (pinfunction "1_1") (pintype "passive"))
      (node (ref "R60") (pin "2") (pinfunction "2_2") (pintype "passive"))
      (node (ref "R61") (pin "2") (pinfunction "2_2") (pintype "passive"))
      (node (ref "R64") (pin "2") (pinfunction "2_2") (pintype "passive"))
      (node (ref "R66") (pin "2") (pinfunction "2_2") (pintype "passive"))
      (node (ref "R68") (pin "1") (pinfunction "1_1") (pintype "passive"))
      (node (ref "R72") (pin "2") (pinfunction "2_2") (pintype "passive"))
      (node (ref "R78") (pin "1") (pinfunction "1_1") (pintype "passive"))
      (node (ref "R79") (pin "1") (pinfunction "1_1") (pintype "passive"))
      (node (ref "R83") (pin "2") (pinfunction "2_2") (pintype "passive"))
      (node (ref "R84") (pin "2") (pinfunction "2_2") (pintype "passive"))
      (node (ref "R87") (pin "2") (pinfunction "2_2") (pintype "passive"))
      (node (ref "R89") (pin "2") (pinfunction "2_2") (pintype "passive"))
      (node (ref "R91") (pin "1") (pinfunction "1_1") (pintype "passive"))
      (node (ref "R95") (pin "2") (pinfunction "2_2") (pintype "passive"))
      (node (ref "T15") (pin "1") (pinfunction "E_1") (pintype "passive"))
      (node (ref "T18") (pin "1") (pinfunction "E_1") (pintype "passive"))
      (node (ref "T21") (pin "1") (pinfunction "E_1") (pintype "passive"))
      (node (ref "T24") (pin "1") (pinfunction "E_1") (pintype "passive"))
      (node (ref "U$1") (pin "14") (pinfunction "VSS_14") (pintype "bidirectional"))
      (node (ref "U$2") (pin "15") (pinfunction "GND_15") (pintype "bidirectional"))
      (node (ref "U$2") (pin "29") (pinfunction "GND_29") (pintype "bidirectional"))
      (node (ref "U$2") (pin "43") (pinfunction "GND_43") (pintype "bidirectional"))
    )
    (net (code "10") (name "Net-(C1-Pad2)") (class "Default")
      (node (ref "C1") (pin "2") (pinfunction "2_2") (pintype "passive"))
      (node (ref "R1") (pin "1") (pinfunction "1_1") (pintype "passive"))
      (node (ref "R2") (pin "2") (pinfunction "2_2") (pintype "passive"))
    )
    (net (code "11") (name "Net-(C5-Pad1)") (class "Default")
      (node (ref "C5") (pin "1") (pinfunction "1_1") (pintype "passive"))
      (node (ref "R12") (pin "1") (pinfunction "1_1") (pintype "passive"))
      (node (ref "R13") (pin "1") (pinfunction "1_1") (pintype "passive"))
      (node (ref "R15") (pin "1") (pinfunction "1_1") (pintype "passive"))
      (node (ref "R8") (pin "2") (pinfunction "2_2") (pintype "passive"))
      (node (ref "R9") (pin "1") (pinfunction "1_1") (pintype "passive"))
    )
    (net (code "12") (name "Net-(C14-Pad2)") (class "Default")
      (node (ref "C14") (pin "2") (pinfunction "2_2") (pintype "passive"))
      (node (ref "R28") (pin "1") (pinfunction "1_1") (pintype "passive"))
      (node (ref "R29") (pin "2") (pinfunction "2_2") (pintype "passive"))
    )
    (net (code "13") (name "Net-(C18-Pad1)") (class "Default")
      (node (ref "C18") (pin "1") (pinfunction "1_1") (pintype "passive"))
      (node (ref "R35") (pin "2") (pinfunction "2_2") (pintype "passive"))
      (node (ref "R36") (pin "1") (pinfunction "1_1") (pintype "passive"))
      (node (ref "R39") (pin "1") (pinfunction "1_1") (pintype "passive"))
      (node (ref "R40") (pin "1") (pinfunction "1_1") (pintype "passive"))
      (node (ref "R42") (pin "1") (pinfunction "1_1") (pintype "passive"))
    )
    (net (code "14") (name "Net-(C25-Pad2)") (class "Default")
      (node (ref "C25") (pin "2") (pinfunction "2_2") (pintype "passive"))
      (node (ref "R51") (pin "1") (pinfunction "1_1") (pintype "passive"))
      (node (ref "R52") (pin "2") (pinfunction "2_2") (pintype "passive"))
    )
    (net (code "15") (name "Net-(C29-Pad1)") (class "Default")
      (node (ref "C29") (pin "1") (pinfunction "1_1") (pintype "passive"))
      (node (ref "R58") (pin "2") (pinfunction "2_2") (pintype "passive"))
      (node (ref "R59") (pin "1") (pinfunction "1_1") (pintype "passive"))
      (node (ref "R62") (pin "1") (pinfunction "1_1") (pintype "passive"))
      (node (ref "R63") (pin "1") (pinfunction "1_1") (pintype "passive"))
      (node (ref "R65") (pin "1") (pinfunction "1_1") (pintype "passive"))
    )
    (net (code "16") (name "Net-(C36-Pad2)") (class "Default")
      (node (ref "C36") (pin "2") (pinfunction "2_2") (pintype "passive"))
      (node (ref "R74") (pin "1") (pinfunction "1_1") (pintype "passive"))
      (node (ref "R75") (pin "2") (pinfunction "2_2") (pintype "passive"))
    )
    (net (code "17") (name "Net-(C40-Pad1)") (class "Default")
      (node (ref "C40") (pin "1") (pinfunction "1_1") (pintype "passive"))
      (node (ref "R81") (pin "2") (pinfunction "2_2") (pintype "passive"))
      (node (ref "R82") (pin "1") (pinfunction "1_1") (pintype "passive"))
      (node (ref "R85") (pin "1") (pinfunction "1_1") (pintype "passive"))
      (node (ref "R86") (pin "1") (pinfunction "1_1") (pintype "passive"))
      (node (ref "R88") (pin "1") (pinfunction "1_1") (pintype "passive"))
    )
    (net (code "18") (name "Net-(D1-C)") (class "Default")
      (node (ref "C4") (pin "2") (pinfunction "2_2") (pintype "passive"))
      (node (ref "D1") (pin "K") (pinfunction "C_K") (pintype "passive"))
      (node (ref "R2") (pin "1") (pinfunction "1_1") (pintype "passive"))
    )
    (net (code "19") (name "Net-(D2-C)") (class "Default")
      (node (ref "C17") (pin "2") (pinfunction "2_2") (pintype "passive"))
      (node (ref "D2") (pin "K") (pinfunction "C_K") (pintype "passive"))
      (node (ref "R29") (pin "1") (pinfunction "1_1") (pintype "passive"))
    )
    (net (code "20") (name "Net-(D3-C)") (class "Default")
      (node (ref "C28") (pin "2") (pinfunction "2_2") (pintype "passive"))
      (node (ref "D3") (pin "K") (pinfunction "C_K") (pintype "passive"))
      (node (ref "R52") (pin "1") (pinfunction "1_1") (pintype "passive"))
    )
    (net (code "21") (name "Net-(D4-C)") (class "Default")
      (node (ref "C39") (pin "2") (pinfunction "2_2") (pintype "passive"))
      (node (ref "D4") (pin "K") (pinfunction "C_K") (pintype "passive"))
      (node (ref "R75") (pin "1") (pinfunction "1_1") (pintype "passive"))
    )
    (net (code "22") (name "Net-(D6-PadA)") (class "Default")
      (node (ref "D6") (pin "A") (pinfunction "A_A") (pintype "passive"))
      (node (ref "JP1") (pin "2") (pinfunction "2_2") (pintype "passive"))
    )
    (net (code "23") (name "Net-(IC2A-+IN)") (class "Default")
      (node (ref "IC2") (pin "5") (pinfunction "+IN_5") (pintype "input"))
      (node (ref "R26") (pin "2") (pinfunction "2_2") (pintype "passive"))
      (node (ref "R73") (pin "2") (pinfunction "2_2") (pintype "passive"))
    )
    (net (code "24") (name "Net-(IC2A--IN)") (class "Default")
      (node (ref "C12") (pin "2") (pinfunction "2_2") (pintype "passive"))
      (node (ref "IC2") (pin "10") (pinfunction "-IN_10") (pintype "input"))
      (node (ref "IC2") (pin "4") (pinfunction "-IN_4") (pintype "input"))
      (node (ref "IC2") (pin "6") (pinfunction "-IN_6") (pintype "input"))
      (node (ref "IC2") (pin "8") (pinfunction "-IN_8") (pintype "input"))
      (node (ref "R24") (pin "1") (pinfunction "1_1") (pintype "passive"))
      (node (ref "R25") (pin "2") (pinfunction "2_2") (pintype "passive"))
    )
    (net (code "25") (name "Net-(IC2B-+IN)") (class "Default")
      (node (ref "IC2") (pin "7") (pinfunction "+IN_7") (pintype "input"))
      (node (ref "R101") (pin "2") (pinfunction "2_2") (pintype "passive"))
      (node (ref "R50") (pin "2") (pinfunction "2_2") (pintype "passive"))
    )
    (net (code "26") (name "Net-(IC2C-+IN)") (class "Default")
      (node (ref "IC2") (pin "9") (pinfunction "+IN_9") (pintype "input"))
      (node (ref "R102") (pin "2") (pinfunction "2_2") (pintype "passive"))
      (node (ref "R23") (pin "2") (pinfunction "2_2") (pintype "passive"))
    )
    (net (code "27") (name "Net-(IC2D-+IN)") (class "Default")
      (node (ref "IC2") (pin "11") (pinfunction "+IN_11") (pintype "input"))
      (node (ref "R103") (pin "2") (pinfunction "2_2") (pintype "passive"))
      (node (ref "R96") (pin "2") (pinfunction "2_2") (pintype "passive"))
    )
    (net (code "28") (name "Net-(JP2-D+)") (class "Default")
      (node (ref "JP2") (pin "3") (pinfunction "D+_3") (pintype "bidirectional"))
      (node (ref "U$1") (pin "13") (pinfunction "D+_13") (pintype "bidirectional"))
    )
    (net (code "29") (name "Net-(JP2-D-)") (class "Default")
      (node (ref "JP2") (pin "2") (pinfunction "D-_2") (pintype "bidirectional"))
      (node (ref "U$1") (pin "12") (pinfunction "D-_12") (pintype "bidirectional"))
    )
    (net (code "30") (name "Net-(JP2-VCC)") (class "Default")
      (node (ref "D5") (pin "A") (pinfunction "A_A") (pintype "passive"))
      (node (ref "JP2") (pin "1") (pinfunction "VCC_1") (pintype "bidirectional"))
    )
    (net (code "31") (name "Net-(JP3-Pad1)") (class "Default")
      (node (ref "JP3") (pin "1") (pinfunction "1_1") (pintype "passive"))
      (node (ref "R104") (pin "2") (pinfunction "2_2") (pintype "passive"))
    )
    (net (code "32") (name "Net-(JP3-Pad2)") (class "Default")
      (node (ref "JP3") (pin "2") (pinfunction "2_2") (pintype "passive"))
      (node (ref "R27") (pin "2") (pinfunction "2_2") (pintype "passive"))
    )
    (net (code "33") (name "Net-(T13A-B)") (class "Default")
      (node (ref "D1") (pin "A") (pinfunction "A_A") (pintype "passive"))
      (node (ref "R3") (pin "1") (pinfunction "1_1") (pintype "passive"))
      (node (ref "R5") (pin "2") (pinfunction "2_2") (pintype "passive"))
      (node (ref "T13") (pin "2") (pinfunction "B_2") (pintype "passive"))
    )
    (net (code "34") (name "Net-(T13A-C)") (class "Default")
      (node (ref "R4") (pin "1") (pinfunction "1_1") (pintype "passive"))
      (node (ref "T13") (pin "5") (pinfunction "B_5") (pintype "passive"))
      (node (ref "T13") (pin "6") (pinfunction "C_6") (pintype "passive"))
    )
    (net (code "35") (name "Net-(T13A-E)") (class "Default")
      (node (ref "C3") (pin "2") (pinfunction "2_2") (pintype "passive"))
      (node (ref "C4") (pin "1") (pinfunction "1_1") (pintype "passive"))
      (node (ref "R6") (pin "2") (pinfunction "2_2") (pintype "passive"))
      (node (ref "T13") (pin "1") (pinfunction "E_1") (pintype "passive"))
      (node (ref "T13") (pin "3") (pinfunction "C_3") (pintype "passive"))
    )
    (net (code "36") (name "Net-(T13B-E)") (class "Default")
      (node (ref "C2") (pin "2") (pinfunction "2_2") (pintype "passive"))
      (node (ref "R1") (pin "2") (pinfunction "2_2") (pintype "passive"))
      (node (ref "R3") (pin "2") (pinfunction "2_2") (pintype "passive"))
      (node (ref "R4") (pin "2") (pinfunction "2_2") (pintype "passive"))
      (node (ref "R7") (pin "2") (pinfunction "2_2") (pintype "passive"))
      (node (ref "T13") (pin "4") (pinfunction "E_4") (pintype "passive"))
    )
    (net (code "37") (name "Net-(T14A-B)") (class "Default")
      (node (ref "C3") (pin "1") (pinfunction "1_1") (pintype "passive"))
      (node (ref "R10") (pin "1") (pinfunction "1_1") (pintype "passive"))
      (node (ref "R9") (pin "2") (pinfunction "2_2") (pintype "passive"))
      (node (ref "T14") (pin "2") (pinfunction "B_2") (pintype "passive"))
    )
    (net (code "38") (name "Net-(T14A-C)") (class "Default")
      (node (ref "C7") (pin "1") (pinfunction "1_1") (pintype "passive"))
      (node (ref "R12") (pin "2") (pinfunction "2_2") (pintype "passive"))
      (node (ref "T14") (pin "6") (pinfunction "C_6") (pintype "passive"))
    )
    (net (code "39") (name "Net-(T14A-E)") (class "Default")
      (node (ref "C6") (pin "1") (pinfunction "1_1") (pintype "passive"))
      (node (ref "R11") (pin "1") (pinfunction "1_1") (pintype "passive"))
      (node (ref "T14") (pin "1") (pinfunction "E_1") (pintype "passive"))
    )
    (net (code "40") (name "Net-(T14B-B)") (class "Default")
      (node (ref "C7") (pin "2") (pinfunction "2_2") (pintype "passive"))
      (node (ref "R13") (pin "2") (pinfunction "2_2") (pintype "passive"))
      (node (ref "R14") (pin "1") (pinfunction "1_1") (pintype "passive"))
      (node (ref "T14") (pin "5") (pinfunction "B_5") (pintype "passive"))
    )
    (net (code "41") (name "Net-(T14B-C)") (class "Default")
      (node (ref "C9") (pin "1") (pinfunction "1_1") (pintype "passive"))
      (node (ref "R16") (pin "1") (pinfunction "1_1") (pintype "passive"))
      (node (ref "T14") (pin "3") (pinfunction "C_3") (pintype "passive"))
    )
    (net (code "42") (name "Net-(T14B-E)") (class "Default")
      (node (ref "C8") (pin "1") (pinfunction "1_1") (pintype "passive"))
      (node (ref "R15") (pin "2") (pinfunction "2_2") (pintype "passive"))
      (node (ref "T14") (pin "4") (pinfunction "E_4") (pintype "passive"))
    )
    (net (code "43") (name "Net-(T15A-B)") (class "Default")
      (node (ref "C9") (pin "2") (pinfunction "2_2") (pintype "passive"))
      (node (ref "R17") (pin "1") (pinfunction "1_1") (pintype "passive"))
      (node (ref "R18") (pin "2") (pinfunction "2_2") (pintype "passive"))
      (node (ref "T15") (pin "2") (pinfunction "B_2") (pintype "passive"))
    )
    (net (code "44") (name "Net-(T15A-C)") (class "Default")
      (node (ref "R19") (pin "2") (pinfunction "2_2") (pintype "passive"))
      (node (ref "T15") (pin "6") (pinfunction "C_6") (pintype "passive"))
    )
    (net (code "45") (name "Net-(T15B-B)") (class "Default")
      (node (ref "C10") (pin "1") (pinfunction "1_1") (pintype "passive"))
      (node (ref "R19") (pin "1") (pinfunction "1_1") (pintype "passive"))
      (node (ref "R20") (pin "2") (pinfunction "2_2") (pintype "passive"))
      (node (ref "T15") (pin "5") (pinfunction "B_5") (pintype "passive"))
    )
    (net (code "46") (name "Net-(T15B-C)") (class "Default")
      (node (ref "R22") (pin "1") (pinfunction "1_1") (pintype "passive"))
      (node (ref "R23") (pin "1") (pinfunction "1_1") (pintype "passive"))
      (node (ref "T15") (pin "3") (pinfunction "C_3") (pintype "passive"))
    )
    (net (code "47") (name "Net-(T15B-E)") (class "Default")
      (node (ref "C11") (pin "1") (pinfunction "1_1") (pintype "passive"))
      (node (ref "R17") (pin "2") (pinfunction "2_2") (pintype "passive"))
      (node (ref "R20") (pin "1") (pinfunction "1_1") (pintype "passive"))
      (node (ref "R21") (pin "2") (pinfunction "2_2") (pintype "passive"))
      (node (ref "T15") (pin "4") (pinfunction "E_4") (pintype "passive"))
    )
    (net (code "48") (name "Net-(T16A-B)") (class "Default")
      (node (ref "D2") (pin "A") (pinfunction "A_A") (pintype "passive"))
      (node (ref "R30") (pin "1") (pinfunction "1_1") (pintype "passive"))
      (node (ref "R32") (pin "2") (pinfunction "2_2") (pintype "passive"))
      (node (ref "T16") (pin "2") (pinfunction "B_2") (pintype "passive"))
    )
    (net (code "49") (name "Net-(T16A-C)") (class "Default")
      (node (ref "R31") (pin "1") (pinfunction "1_1") (pintype "passive"))
      (node (ref "T16") (pin "5") (pinfunction "B_5") (pintype "passive"))
      (node (ref "T16") (pin "6") (pinfunction "C_6") (pintype "passive"))
    )
    (net (code "50") (name "Net-(T16A-E)") (class "Default")
      (node (ref "C16") (pin "2") (pinfunction "2_2") (pintype "passive"))
      (node (ref "C17") (pin "1") (pinfunction "1_1") (pintype "passive"))
      (node (ref "R33") (pin "2") (pinfunction "2_2") (pintype "passive"))
      (node (ref "T16") (pin "1") (pinfunction "E_1") (pintype "passive"))
      (node (ref "T16") (pin "3") (pinfunction "C_3") (pintype "passive"))
    )
    (net (code "51") (name "Net-(T16B-E)") (class "Default")
      (node (ref "C15") (pin "2") (pinfunction "2_2") (pintype "passive"))
      (node (ref "R28") (pin "2") (pinfunction "2_2") (pintype "passive"))
      (node (ref "R30") (pin "2") (pinfunction "2_2") (pintype "passive"))
      (node (ref "R31") (pin "2") (pinfunction "2_2") (pintype "passive"))
      (node (ref "R34") (pin "2") (pinfunction "2_2") (pintype "passive"))
      (node (ref "T16") (pin "4") (pinfunction "E_4") (pintype "passive"))
    )
    (net (code "52") (name "Net-(T17A-B)") (class "Default")
      (node (ref "C16") (pin "1") (pinfunction "1_1") (pintype "passive"))
      (node (ref "R36") (pin "2") (pinfunction "2_2") (pintype "passive"))
      (node (ref "R37") (pin "1") (pinfunction "1_1") (pintype "passive"))
      (node (ref "T17") (pin "2") (pinfunction "B_2") (pintype "passive"))
    )
    (net (code "53") (name "Net-(T17A-C)") (class "Default")
      (node (ref "C20") (pin "1") (pinfunction "1_1") (pintype "passive"))
      (node (ref "R39") (pin "2") (pinfunction "2_2") (pintype "passive"))
      (node (ref "T17") (pin "6") (pinfunction "C_6") (pintype "passive"))
    )
    (net (code "54") (name "Net-(T17A-E)") (class "Default")
      (node (ref "C19") (pin "1") (pinfunction "1_1") (pintype "passive"))
      (node (ref "R38") (pin "1") (pinfunction "1_1") (pintype "passive"))
      (node (ref "T17") (pin "1") (pinfunction "E_1") (pintype "passive"))
    )
    (net (code "55") (name "Net-(T17B-B)") (class "Default")
      (node (ref "C20") (pin "2") (pinfunction "2_2") (pintype "passive"))
      (node (ref "R40") (pin "2") (pinfunction "2_2") (pintype "passive"))
      (node (ref "R41") (pin "1") (pinfunction "1_1") (pintype "passive"))
      (node (ref "T17") (pin "5") (pinfunction "B_5") (pintype "passive"))
    )
    (net (code "56") (name "Net-(T17B-C)") (class "Default")
      (node (ref "C22") (pin "1") (pinfunction "1_1") (pintype "passive"))
      (node (ref "R43") (pin "1") (pinfunction "1_1") (pintype "passive"))
      (node (ref "T17") (pin "3") (pinfunction "C_3") (pintype "passive"))
    )
    (net (code "57") (name "Net-(T17B-E)") (class "Default")
      (node (ref "C21") (pin "1") (pinfunction "1_1") (pintype "passive"))
      (node (ref "R42") (pin "2") (pinfunction "2_2") (pintype "passive"))
      (node (ref "T17") (pin "4") (pinfunction "E_4") (pintype "passive"))
    )
    (net (code "58") (name "Net-(T18A-B)") (class "Default")
      (node (ref "C22") (pin "2") (pinfunction "2_2") (pintype "passive"))
      (node (ref "R44") (pin "1") (pinfunction "1_1") (pintype "passive"))
      (node (ref "R45") (pin "2") (pinfunction "2_2") (pintype "passive"))
      (node (ref "T18") (pin "2") (pinfunction "B_2") (pintype "passive"))
    )
    (net (code "59") (name "Net-(T18A-C)") (class "Default")
      (node (ref "R46") (pin "2") (pinfunction "2_2") (pintype "passive"))
      (node (ref "T18") (pin "6") (pinfunction "C_6") (pintype "passive"))
    )
    (net (code "60") (name "Net-(T18B-B)") (class "Default")
      (node (ref "C23") (pin "1") (pinfunction "1_1") (pintype "passive"))
      (node (ref "R46") (pin "1") (pinfunction "1_1") (pintype "passive"))
      (node (ref "R47") (pin "2") (pinfunction "2_2") (pintype "passive"))
      (node (ref "T18") (pin "5") (pinfunction "B_5") (pintype "passive"))
    )
    (net (code "61") (name "Net-(T18B-C)") (class "Default")
      (node (ref "R49") (pin "1") (pinfunction "1_1") (pintype "passive"))
      (node (ref "R50") (pin "1") (pinfunction "1_1") (pintype "passive"))
      (node (ref "T18") (pin "3") (pinfunction "C_3") (pintype "passive"))
    )
    (net (code "62") (name "Net-(T18B-E)") (class "Default")
      (node (ref "C24") (pin "1") (pinfunction "1_1") (pintype "passive"))
      (node (ref "R44") (pin "2") (pinfunction "2_2") (pintype "passive"))
      (node (ref "R47") (pin "1") (pinfunction "1_1") (pintype "passive"))
      (node (ref "R48") (pin "2") (pinfunction "2_2") (pintype "passive"))
      (node (ref "T18") (pin "4") (pinfunction "E_4") (pintype "passive"))
    )
    (net (code "63") (name "Net-(T19A-B)") (class "Default")
      (node (ref "D3") (pin "A") (pinfunction "A_A") (pintype "passive"))
      (node (ref "R53") (pin "1") (pinfunction "1_1") (pintype "passive"))
      (node (ref "R55") (pin "2") (pinfunction "2_2") (pintype "passive"))
      (node (ref "T19") (pin "2") (pinfunction "B_2") (pintype "passive"))
    )
    (net (code "64") (name "Net-(T19A-C)") (class "Default")
      (node (ref "R54") (pin "1") (pinfunction "1_1") (pintype "passive"))
      (node (ref "T19") (pin "5") (pinfunction "B_5") (pintype "passive"))
      (node (ref "T19") (pin "6") (pinfunction "C_6") (pintype "passive"))
    )
    (net (code "65") (name "Net-(T19A-E)") (class "Default")
      (node (ref "C27") (pin "2") (pinfunction "2_2") (pintype "passive"))
      (node (ref "C28") (pin "1") (pinfunction "1_1") (pintype "passive"))
      (node (ref "R56") (pin "2") (pinfunction "2_2") (pintype "passive"))
      (node (ref "T19") (pin "1") (pinfunction "E_1") (pintype "passive"))
      (node (ref "T19") (pin "3") (pinfunction "C_3") (pintype "passive"))
    )
    (net (code "66") (name "Net-(T19B-E)") (class "Default")
      (node (ref "C26") (pin "2") (pinfunction "2_2") (pintype "passive"))
      (node (ref "R51") (pin "2") (pinfunction "2_2") (pintype "passive"))
      (node (ref "R53") (pin "2") (pinfunction "2_2") (pintype "passive"))
      (node (ref "R54") (pin "2") (pinfunction "2_2") (pintype "passive"))
      (node (ref "R57") (pin "2") (pinfunction "2_2") (pintype "passive"))
      (node (ref "T19") (pin "4") (pinfunction "E_4") (pintype "passive"))
    )
    (net (code "67") (name "Net-(T20A-B)") (class "Default")
      (node (ref "C27") (pin "1") (pinfunction "1_1") (pintype "passive"))
      (node (ref "R59") (pin "2") (pinfunction "2_2") (pintype "passive"))
      (node (ref "R60") (pin "1") (pinfunction "1_1") (pintype "passive"))
      (node (ref "T20") (pin "2") (pinfunction "B_2") (pintype "passive"))
    )
    (net (code "68") (name "Net-(T20A-C)") (class "Default")
      (node (ref "C31") (pin "1") (pinfunction "1_1") (pintype "passive"))
      (node (ref "R62") (pin "2") (pinfunction "2_2") (pintype "passive"))
      (node (ref "T20") (pin "6") (pinfunction "C_6") (pintype "passive"))
    )
    (net (code "69") (name "Net-(T20A-E)") (class "Default")
      (node (ref "C30") (pin "1") (pinfunction "1_1") (pintype "passive"))
      (node (ref "R61") (pin "1") (pinfunction "1_1") (pintype "passive"))
      (node (ref "T20") (pin "1") (pinfunction "E_1") (pintype "passive"))
    )
    (net (code "70") (name "Net-(T20B-B)") (class "Default")
      (node (ref "C31") (pin "2") (pinfunction "2_2") (pintype "passive"))
      (node (ref "R63") (pin "2") (pinfunction "2_2") (pintype "passive"))
      (node (ref "R64") (pin "1") (pinfunction "1_1") (pintype "passive"))
      (node (ref "T20") (pin "5") (pinfunction "B_5") (pintype "passive"))
    )
    (net (code "71") (name "Net-(T20B-C)") (class "Default")
      (node (ref "C33") (pin "1") (pinfunction "1_1") (pintype "passive"))
      (node (ref "R66") (pin "1") (pinfunction "1_1") (pintype "passive"))
      (node (ref "T20") (pin "3") (pinfunction "C_3") (pintype "passive"))
    )
    (net (code "72") (name "Net-(T20B-E)") (class "Default")
      (node (ref "C32") (pin "1") (pinfunction "1_1") (pintype "passive"))
      (node (ref "R65") (pin "2") (pinfunction "2_2") (pintype "passive"))
      (node (ref "T20") (pin "4") (pinfunction "E_4") (pintype "passive"))
    )
    (net (code "73") (name "Net-(T21A-B)") (class "Default")
      (node (ref "C33") (pin "2") (pinfunction "2_2") (pintype "passive"))
      (node (ref "R67") (pin "1") (pinfunction "1_1") (pintype "passive"))
      (node (ref "R68") (pin "2") (pinfunction "2_2") (pintype "passive"))
      (node (ref "T21") (pin "2") (pinfunction "B_2") (pintype "passive"))
    )
    (net (code "74") (name "Net-(T21A-C)") (class "Default")
      (node (ref "R69") (pin "2") (pinfunction "2_2") (pintype "passive"))
      (node (ref "T21") (pin "6") (pinfunction "C_6") (pintype "passive"))
    )
    (net (code "75") (name "Net-(T21B-B)") (class "Default")
      (node (ref "C34") (pin "1") (pinfunction "1_1") (pintype "passive"))
      (node (ref "R69") (pin "1") (pinfunction "1_1") (pintype "passive"))
      (node (ref "R70") (pin "2") (pinfunction "2_2") (pintype "passive"))
      (node (ref "T21") (pin "5") (pinfunction "B_5") (pintype "passive"))
    )
    (net (code "76") (name "Net-(T21B-C)") (class "Default")
      (node (ref "R72") (pin "1") (pinfunction "1_1") (pintype "passive"))
      (node (ref "R73") (pin "1") (pinfunction "1_1") (pintype "passive"))
      (node (ref "T21") (pin "3") (pinfunction "C_3") (pintype "passive"))
    )
    (net (code "77") (name "Net-(T21B-E)") (class "Default")
      (node (ref "C35") (pin "1") (pinfunction "1_1") (pintype "passive"))
      (node (ref "R67") (pin "2") (pinfunction "2_2") (pintype "passive"))
      (node (ref "R70") (pin "1") (pinfunction "1_1") (pintype "passive"))
      (node (ref "R71") (pin "2") (pinfunction "2_2") (pintype "passive"))
      (node (ref "T21") (pin "4") (pinfunction "E_4") (pintype "passive"))
    )
    (net (code "78") (name "Net-(T22A-B)") (class "Default")
      (node (ref "D4") (pin "A") (pinfunction "A_A") (pintype "passive"))
      (node (ref "R76") (pin "1") (pinfunction "1_1") (pintype "passive"))
      (node (ref "R78") (pin "2") (pinfunction "2_2") (pintype "passive"))
      (node (ref "T22") (pin "2") (pinfunction "B_2") (pintype "passive"))
    )
    (net (code "79") (name "Net-(T22A-C)") (class "Default")
      (node (ref "R77") (pin "1") (pinfunction "1_1") (pintype "passive"))
      (node (ref "T22") (pin "5") (pinfunction "B_5") (pintype "passive"))
      (node (ref "T22") (pin "6") (pinfunction "C_6") (pintype "passive"))
    )
    (net (code "80") (name "Net-(T22A-E)") (class "Default")
      (node (ref "C38") (pin "2") (pinfunction "2_2") (pintype "passive"))
      (node (ref "C39") (pin "1") (pinfunction "1_1") (pintype "passive"))
      (node (ref "R79") (pin "2") (pinfunction "2_2") (pintype "passive"))
      (node (ref "T22") (pin "1") (pinfunction "E_1") (pintype "passive"))
      (node (ref "T22") (pin "3") (pinfunction "C_3") (pintype "passive"))
    )
    (net (code "81") (name "Net-(T22B-E)") (class "Default")
      (node (ref "C37") (pin "2") (pinfunction "2_2") (pintype "passive"))
      (node (ref "R74") (pin "2") (pinfunction "2_2") (pintype "passive"))
      (node (ref "R76") (pin "2") (pinfunction "2_2") (pintype "passive"))
      (node (ref "R77") (pin "2") (pinfunction "2_2") (pintype "passive"))
      (node (ref "R80") (pin "2") (pinfunction "2_2") (pintype "passive"))
      (node (ref "T22") (pin "4") (pinfunction "E_4") (pintype "passive"))
    )
    (net (code "82") (name "Net-(T23A-B)") (class "Default")
      (node (ref "C38") (pin "1") (pinfunction "1_1") (pintype "passive"))
      (node (ref "R82") (pin "2") (pinfunction "2_2") (pintype "passive"))
      (node (ref "R83") (pin "1") (pinfunction "1_1") (pintype "passive"))
      (node (ref "T23") (pin "2") (pinfunction "B_2") (pintype "passive"))
    )
    (net (code "83") (name "Net-(T23A-C)") (class "Default")
      (node (ref "C42") (pin "1") (pinfunction "1_1") (pintype "passive"))
      (node (ref "R85") (pin "2") (pinfunction "2_2") (pintype "passive"))
      (node (ref "T23") (pin "6") (pinfunction "C_6") (pintype "passive"))
    )
    (net (code "84") (name "Net-(T23A-E)") (class "Default")
      (node (ref "C41") (pin "1") (pinfunction "1_1") (pintype "passive"))
      (node (ref "R84") (pin "1") (pinfunction "1_1") (pintype "passive"))
      (node (ref "T23") (pin "1") (pinfunction "E_1") (pintype "passive"))
    )
    (net (code "85") (name "Net-(T23B-B)") (class "Default")
      (node (ref "C42") (pin "2") (pinfunction "2_2") (pintype "passive"))
      (node (ref "R86") (pin "2") (pinfunction "2_2") (pintype "passive"))
      (node (ref "R87") (pin "1") (pinfunction "1_1") (pintype "passive"))
      (node (ref "T23") (pin "5") (pinfunction "B_5") (pintype "passive"))
    )
    (net (code "86") (name "Net-(T23B-C)") (class "Default")
      (node (ref "C44") (pin "1") (pinfunction "1_1") (pintype "passive"))
      (node (ref "R89") (pin "1") (pinfunction "1_1") (pintype "passive"))
      (node (ref "T23") (pin "3") (pinfunction "C_3") (pintype "passive"))
    )
    (net (code "87") (name "Net-(T23B-E)") (class "Default")
      (node (ref "C43") (pin "1") (pinfunction "1_1") (pintype "passive"))
      (node (ref "R88") (pin "2") (pinfunction "2_2") (pintype "passive"))
      (node (ref "T23") (pin "4") (pinfunction "E_4") (pintype "passive"))
    )
    (net (code "88") (name "Net-(T24A-B)") (class "Default")
      (node (ref "C44") (pin "2") (pinfunction "2_2") (pintype "passive"))
      (node (ref "R90") (pin "1") (pinfunction "1_1") (pintype "passive"))
      (node (ref "R91") (pin "2") (pinfunction "2_2") (pintype "passive"))
      (node (ref "T24") (pin "2") (pinfunction "B_2") (pintype "passive"))
    )
    (net (code "89") (name "Net-(T24A-C)") (class "Default")
      (node (ref "R92") (pin "2") (pinfunction "2_2") (pintype "passive"))
      (node (ref "T24") (pin "6") (pinfunction "C_6") (pintype "passive"))
    )
    (net (code "90") (name "Net-(T24B-B)") (class "Default")
      (node (ref "C45") (pin "1") (pinfunction "1_1") (pintype "passive"))
      (node (ref "R92") (pin "1") (pinfunction "1_1") (pintype "passive"))
      (node (ref "R93") (pin "2") (pinfunction "2_2") (pintype "passive"))
      (node (ref "T24") (pin "5") (pinfunction "B_5") (pintype "passive"))
    )
    (net (code "91") (name "Net-(T24B-C)") (class "Default")
      (node (ref "R95") (pin "1") (pinfunction "1_1") (pintype "passive"))
      (node (ref "R96") (pin "1") (pinfunction "1_1") (pintype "passive"))
      (node (ref "T24") (pin "3") (pinfunction "C_3") (pintype "passive"))
    )
    (net (code "92") (name "Net-(T24B-E)") (class "Default")
      (node (ref "C46") (pin "1") (pinfunction "1_1") (pintype "passive"))
      (node (ref "R90") (pin "2") (pinfunction "2_2") (pintype "passive"))
      (node (ref "R93") (pin "1") (pinfunction "1_1") (pintype "passive"))
      (node (ref "R94") (pin "2") (pinfunction "2_2") (pintype "passive"))
      (node (ref "T24") (pin "4") (pinfunction "E_4") (pintype "passive"))
    )
    (net (code "93") (name "Net-(U$2-UPDI)") (class "Default")
      (node (ref "TP1") (pin "TP") (pinfunction "TP_TP") (pintype "input"))
      (node (ref "U$2") (pin "41") (pinfunction "UPDI_41") (pintype "bidirectional"))
    )
    (net (code "94") (name "unconnected-(IC1-CB-Pad4)") (class "Default")
      (node (ref "IC1") (pin "4") (pinfunction "CB_4") (pintype "input"))
    )
    (net (code "95") (name "unconnected-(JP2-ID-Pad4)") (class "Default")
      (node (ref "JP2") (pin "4") (pinfunction "ID_4") (pintype "bidirectional"))
    )
    (net (code "96") (name "unconnected-(U$1-GP0-Pad2)") (class "Default")
      (node (ref "U$1") (pin "2") (pinfunction "GP0_2") (pintype "bidirectional"))
    )
    (net (code "97") (name "unconnected-(U$1-GP1-Pad3)") (class "Default")
      (node (ref "U$1") (pin "3") (pinfunction "GP1_3") (pintype "bidirectional"))
    )
    (net (code "98") (name "unconnected-(U$1-GP2-Pad7)") (class "Default")
      (node (ref "U$1") (pin "7") (pinfunction "GP2_7") (pintype "bidirectional"))
    )
    (net (code "99") (name "unconnected-(U$1-GP3-Pad8)") (class "Default")
      (node (ref "U$1") (pin "8") (pinfunction "GP3_8") (pintype "bidirectional"))
    )
    (net (code "100") (name "unconnected-(U$1-SCL-Pad10)") (class "Default")
      (node (ref "U$1") (pin "10") (pinfunction "SCL_10") (pintype "bidirectional"))
    )
    (net (code "101") (name "unconnected-(U$1-SDA-Pad9)") (class "Default")
      (node (ref "U$1") (pin "9") (pinfunction "SDA_9") (pintype "bidirectional"))
    )
    (net (code "102") (name "unconnected-(U$1-VUSB-Pad11)") (class "Default")
      (node (ref "U$1") (pin "11") (pinfunction "VUSB_11") (pintype "bidirectional"))
    )
    (net (code "103") (name "unconnected-(U$1-{slash}RST-Pad4)") (class "Default")
      (node (ref "U$1") (pin "4") (pinfunction "/RST_4") (pintype "bidirectional"))
    )
    (net (code "104") (name "unconnected-(U$2-PA2-Pad46)") (class "Default")
      (node (ref "U$2") (pin "46") (pinfunction "PA2_46") (pintype "bidirectional"))
    )
    (net (code "105") (name "unconnected-(U$2-PA3-Pad47)") (class "Default")
      (node (ref "U$2") (pin "47") (pinfunction "PA3_47") (pintype "bidirectional"))
    )
    (net (code "106") (name "unconnected-(U$2-PB1-Pad5)") (class "Default")
      (node (ref "U$2") (pin "5") (pinfunction "PB1_5") (pintype "bidirectional"))
    )
    (net (code "107") (name "unconnected-(U$2-PB2-Pad6)") (class "Default")
      (node (ref "U$2") (pin "6") (pinfunction "PB2_6") (pintype "bidirectional"))
    )
    (net (code "108") (name "unconnected-(U$2-PB3-Pad7)") (class "Default")
      (node (ref "U$2") (pin "7") (pinfunction "PB3_7") (pintype "bidirectional"))
    )
    (net (code "109") (name "unconnected-(U$2-PB4-Pad8)") (class "Default")
      (node (ref "U$2") (pin "8") (pinfunction "PB4_8") (pintype "bidirectional"))
    )
    (net (code "110") (name "unconnected-(U$2-PB5-Pad9)") (class "Default")
      (node (ref "U$2") (pin "9") (pinfunction "PB5_9") (pintype "bidirectional"))
    )
    (net (code "111") (name "unconnected-(U$2-PC1-Pad11)") (class "Default")
      (node (ref "U$2") (pin "11") (pinfunction "PC1_11") (pintype "bidirectional"))
    )
    (net (code "112") (name "unconnected-(U$2-PC2-Pad12)") (class "Default")
      (node (ref "U$2") (pin "12") (pinfunction "PC2_12") (pintype "bidirectional"))
    )
    (net (code "113") (name "unconnected-(U$2-PC3-Pad13)") (class "Default")
      (node (ref "U$2") (pin "13") (pinfunction "PC3_13") (pintype "bidirectional"))
    )
    (net (code "114") (name "unconnected-(U$2-PC4-Pad16)") (class "Default")
      (node (ref "U$2") (pin "16") (pinfunction "PC4_16") (pintype "bidirectional"))
    )
    (net (code "115") (name "unconnected-(U$2-PC5-Pad17)") (class "Default")
      (node (ref "U$2") (pin "17") (pinfunction "PC5_17") (pintype "bidirectional"))
    )
    (net (code "116") (name "unconnected-(U$2-PC6-Pad18)") (class "Default")
      (node (ref "U$2") (pin "18") (pinfunction "PC6_18") (pintype "bidirectional"))
    )
    (net (code "117") (name "unconnected-(U$2-PC7-Pad19)") (class "Default")
      (node (ref "U$2") (pin "19") (pinfunction "PC7_19") (pintype "bidirectional"))
    )
    (net (code "118") (name "unconnected-(U$2-PD1-Pad21)") (class "Default")
      (node (ref "U$2") (pin "21") (pinfunction "PD1_21") (pintype "bidirectional"))
    )
    (net (code "119") (name "unconnected-(U$2-PD2-Pad22)") (class "Default")
      (node (ref "U$2") (pin "22") (pinfunction "PD2_22") (pintype "bidirectional"))
    )
    (net (code "120") (name "unconnected-(U$2-PD3-Pad23)") (class "Default")
      (node (ref "U$2") (pin "23") (pinfunction "PD3_23") (pintype "bidirectional"))
    )
    (net (code "121") (name "unconnected-(U$2-PD4-Pad24)") (class "Default")
      (node (ref "U$2") (pin "24") (pinfunction "PD4_24") (pintype "bidirectional"))
    )
    (net (code "122") (name "unconnected-(U$2-PD5-Pad25)") (class "Default")
      (node (ref "U$2") (pin "25") (pinfunction "PD5_25") (pintype "bidirectional"))
    )
    (net (code "123") (name "unconnected-(U$2-PD6-Pad26)") (class "Default")
      (node (ref "U$2") (pin "26") (pinfunction "PD6_26") (pintype "bidirectional"))
    )
    (net (code "124") (name "unconnected-(U$2-PD7-Pad27)") (class "Default")
      (node (ref "U$2") (pin "27") (pinfunction "PD7_27") (pintype "bidirectional"))
    )
    (net (code "125") (name "unconnected-(U$2-PE1-Pad31)") (class "Default")
      (node (ref "U$2") (pin "31") (pinfunction "PE1_31") (pintype "bidirectional"))
    )
    (net (code "126") (name "unconnected-(U$2-PE2-Pad32)") (class "Default")
      (node (ref "U$2") (pin "32") (pinfunction "PE2_32") (pintype "bidirectional"))
    )
    (net (code "127") (name "unconnected-(U$2-PE3-Pad33)") (class "Default")
      (node (ref "U$2") (pin "33") (pinfunction "PE3_33") (pintype "bidirectional"))
    )
    (net (code "128") (name "unconnected-(U$2-PF0-Pad34)") (class "Default")
      (node (ref "U$2") (pin "34") (pinfunction "PF0_34") (pintype "bidirectional"))
    )
    (net (code "129") (name "unconnected-(U$2-PF1-Pad35)") (class "Default")
      (node (ref "U$2") (pin "35") (pinfunction "PF1_35") (pintype "bidirectional"))
    )
    (net (code "130") (name "unconnected-(U$2-PF2-Pad36)") (class "Default")
      (node (ref "U$2") (pin "36") (pinfunction "PF2_36") (pintype "bidirectional"))
    )
    (net (code "131") (name "unconnected-(U$2-PF3-Pad37)") (class "Default")
      (node (ref "U$2") (pin "37") (pinfunction "PF3_37") (pintype "bidirectional"))
    )
    (net (code "132") (name "unconnected-(U$2-PF4-Pad38)") (class "Default")
      (node (ref "U$2") (pin "38") (pinfunction "PF4_38") (pintype "bidirectional"))
    )
    (net (code "133") (name "unconnected-(U$2-PF5-Pad39)") (class "Default")
      (node (ref "U$2") (pin "39") (pinfunction "PF5_39") (pintype "bidirectional"))
    )
    (net (code "134") (name "unconnected-(U$2-PF6-Pad40)") (class "Default")
      (node (ref "U$2") (pin "40") (pinfunction "PF6_40") (pintype "bidirectional"))
    )
  )
)
